# MbrdA_rev2_180.net
KiCad netlist of a schematic drawn in EAGLE
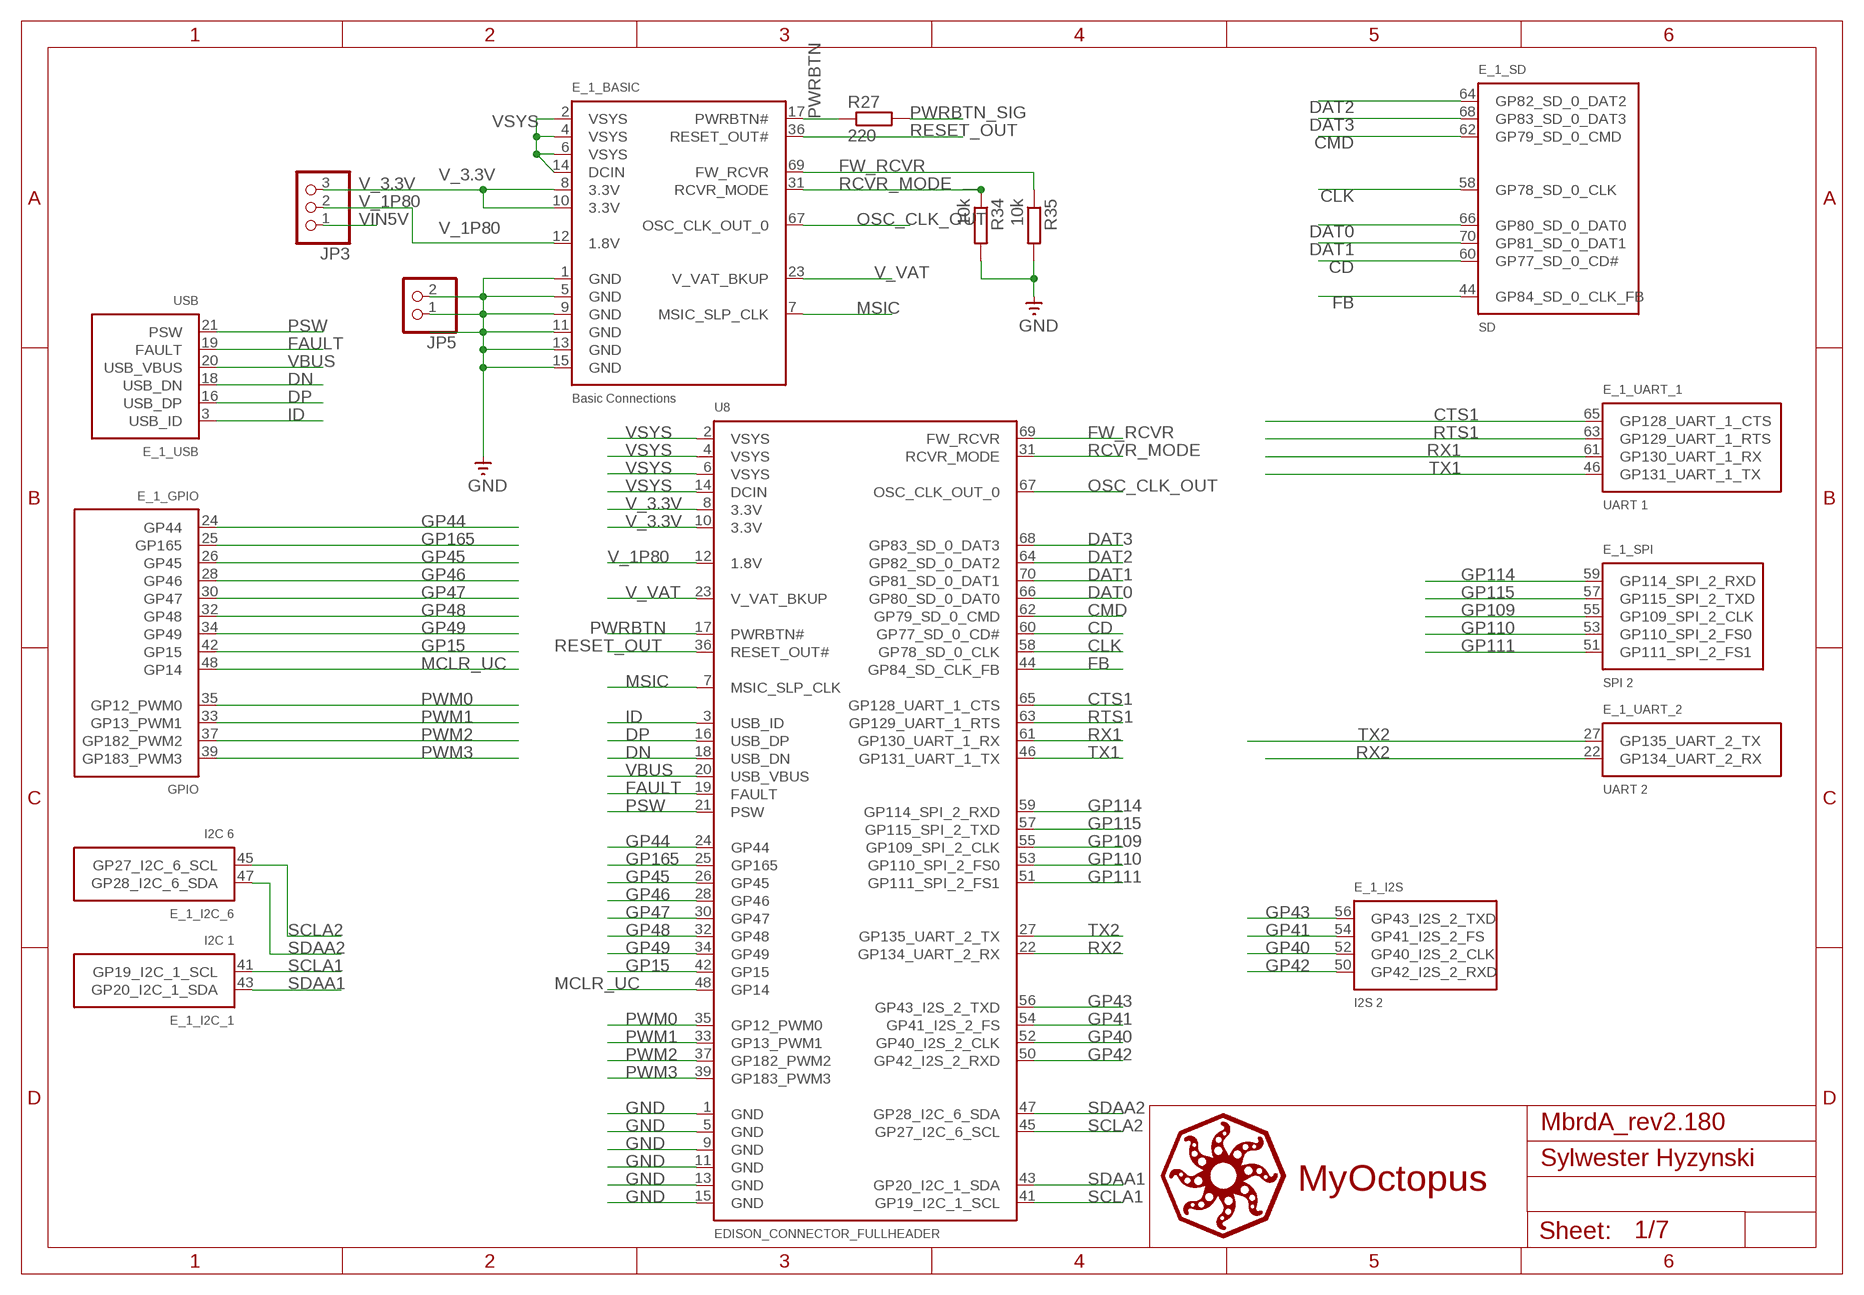
[diagram p0: schematic, sheet 1]
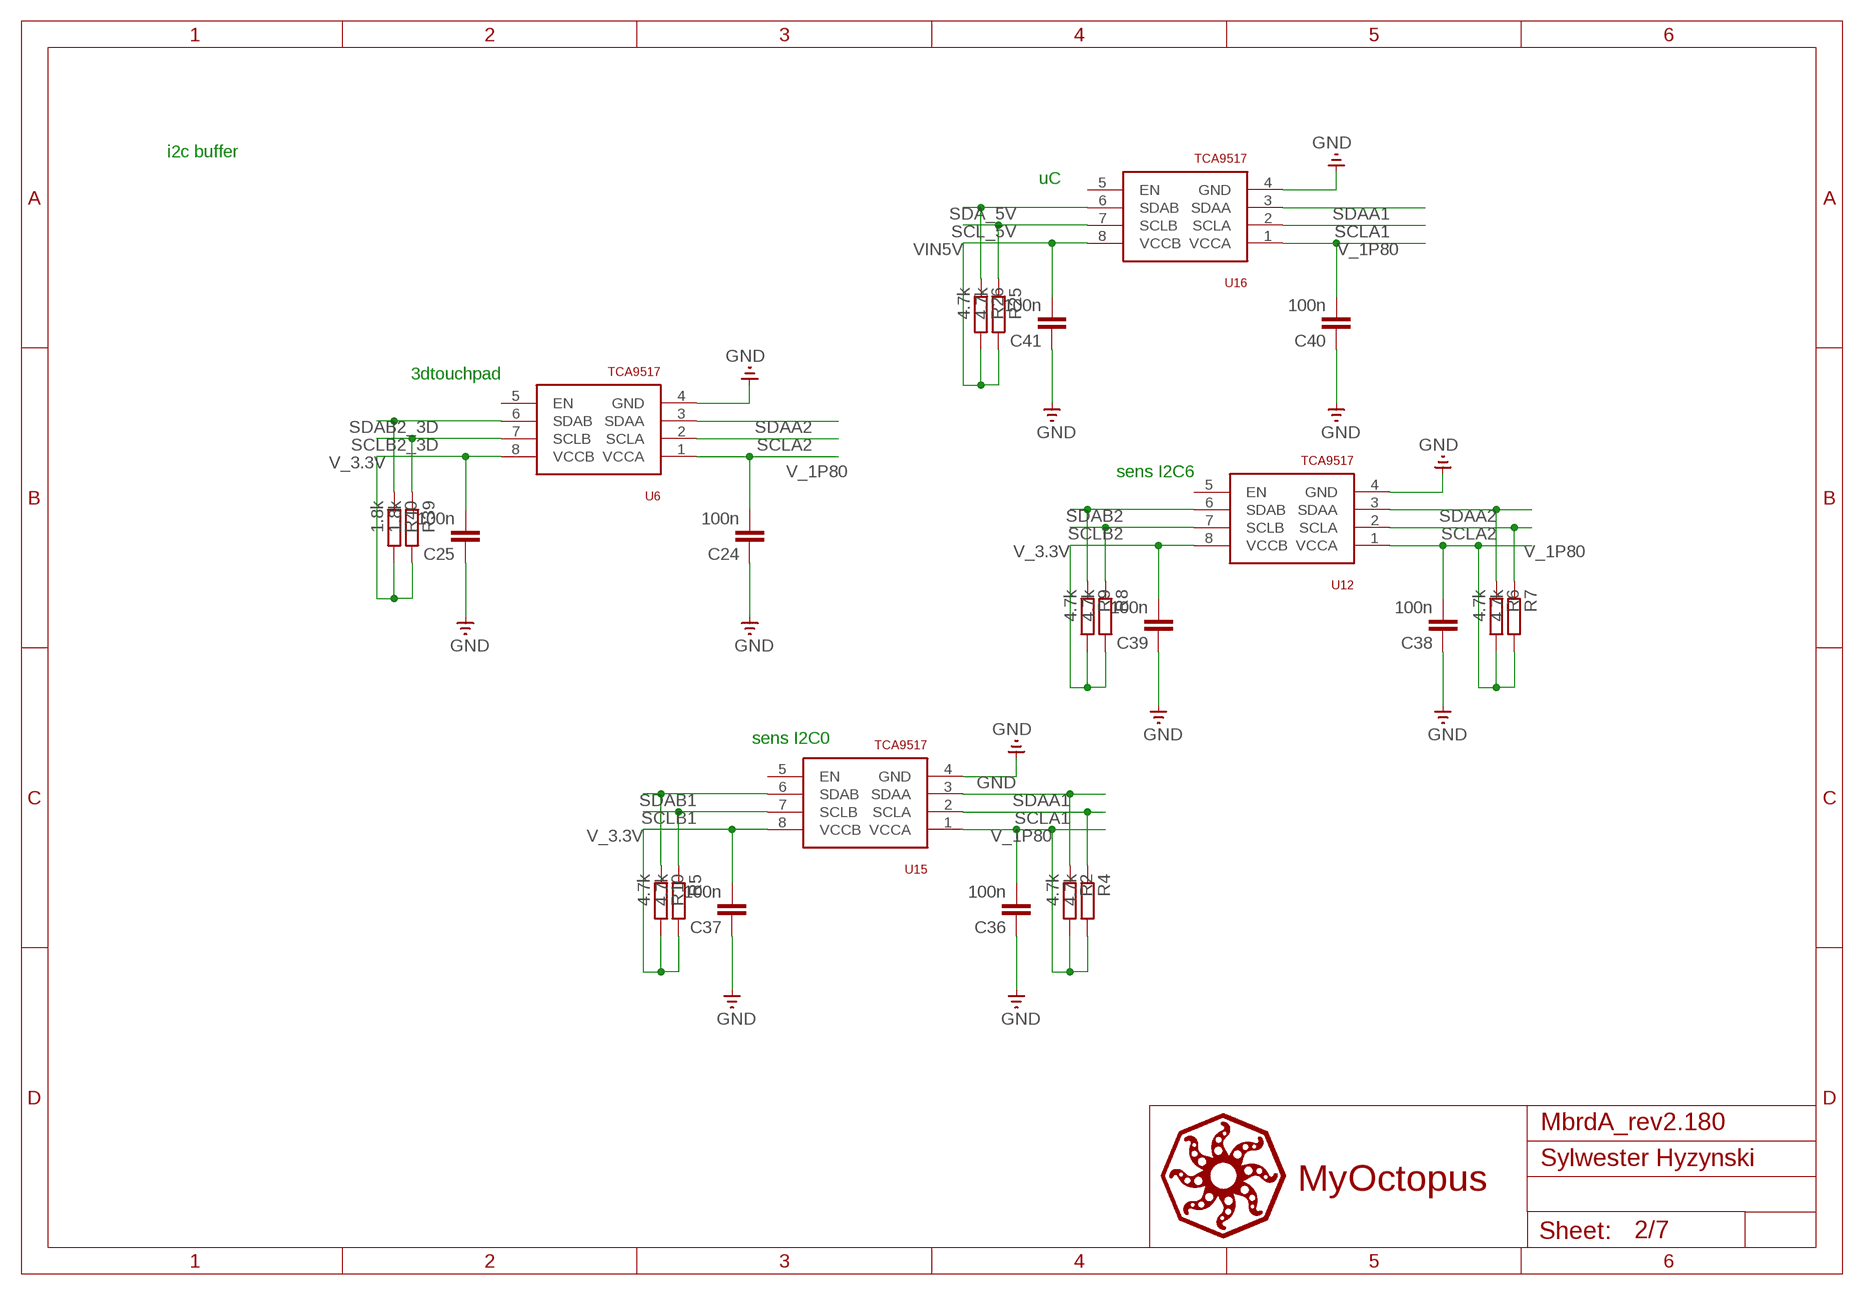
[diagram p1: schematic, sheet 2]
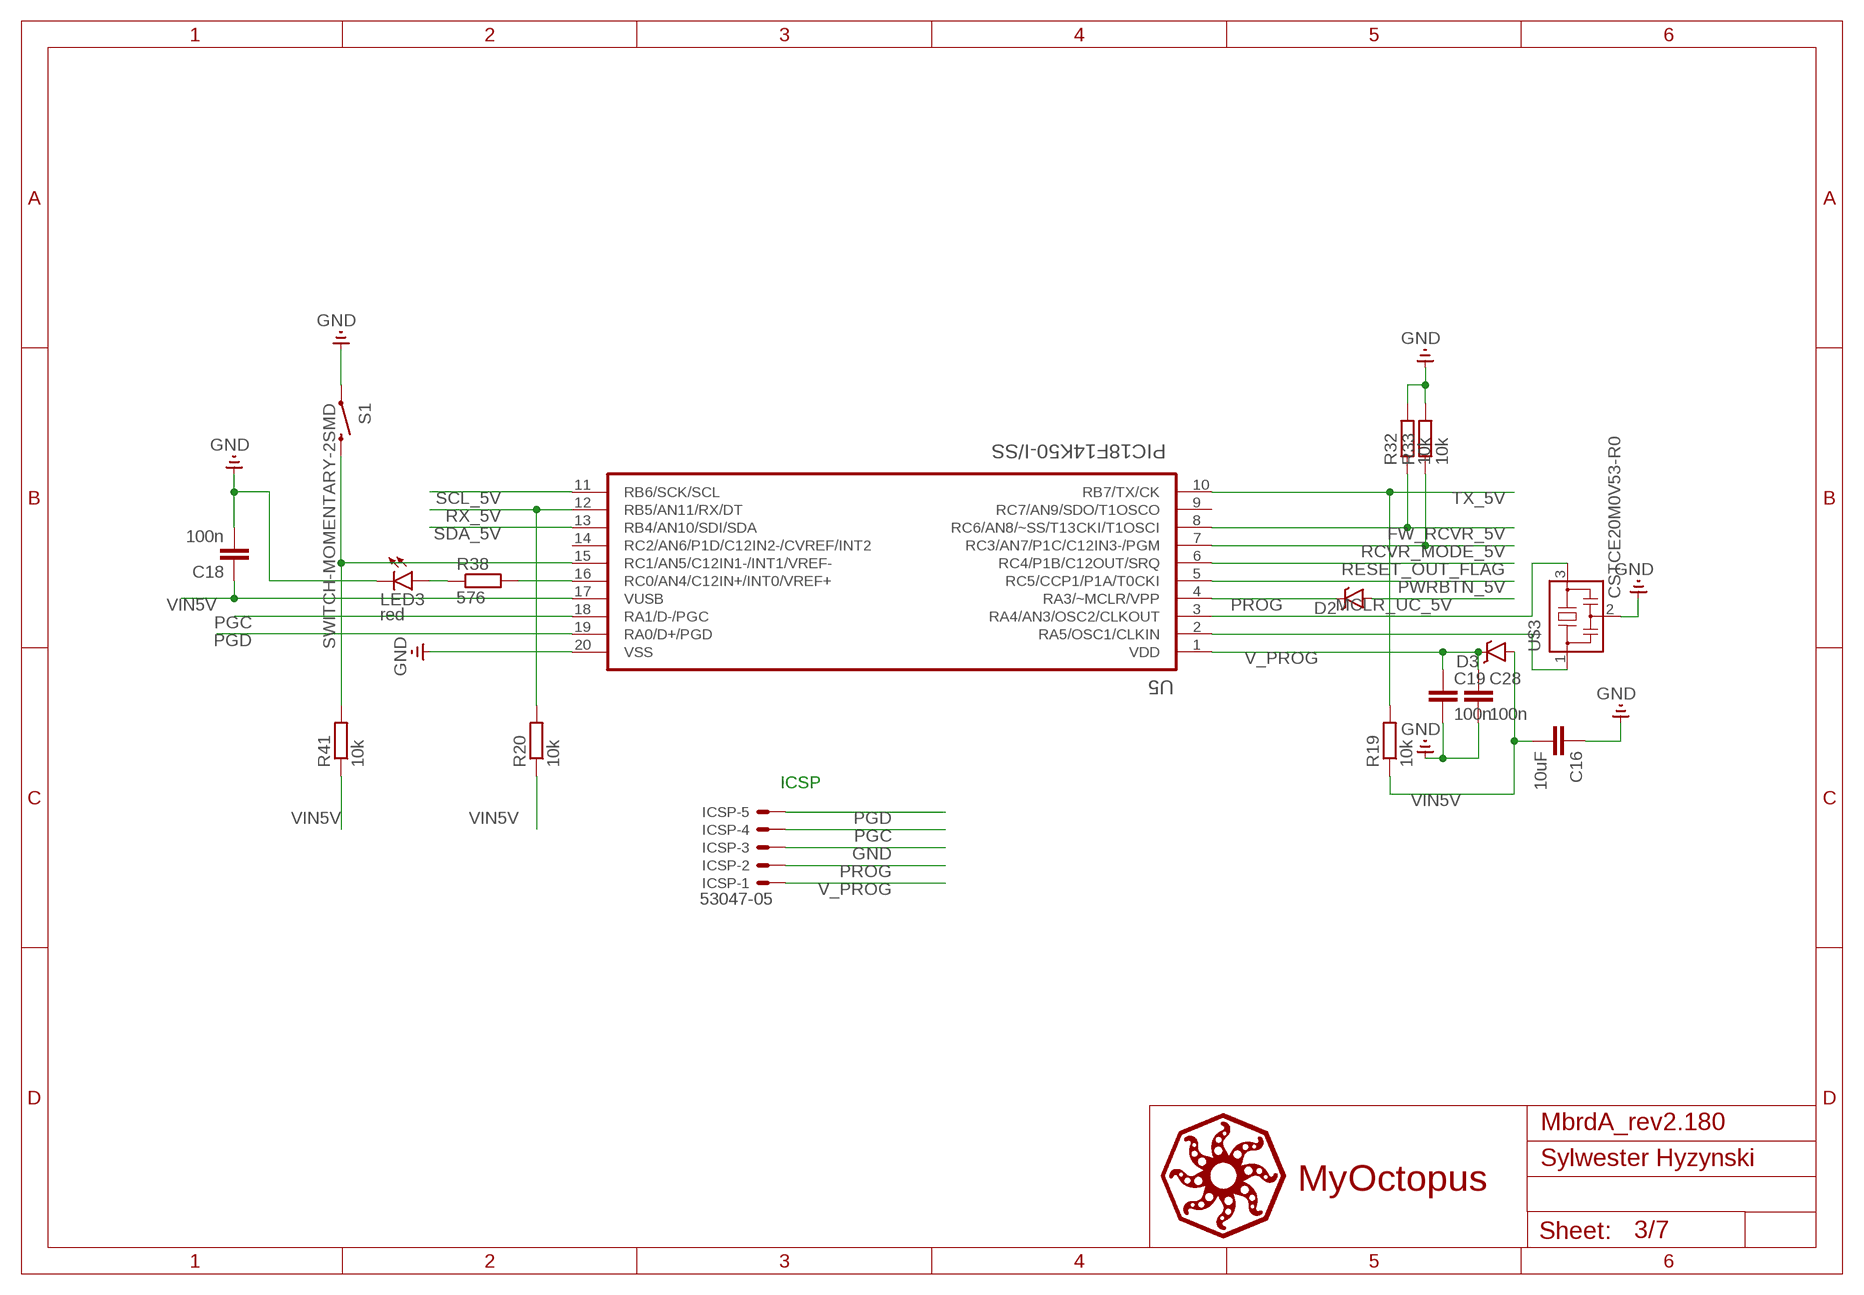
[diagram p2: schematic, sheet 3]
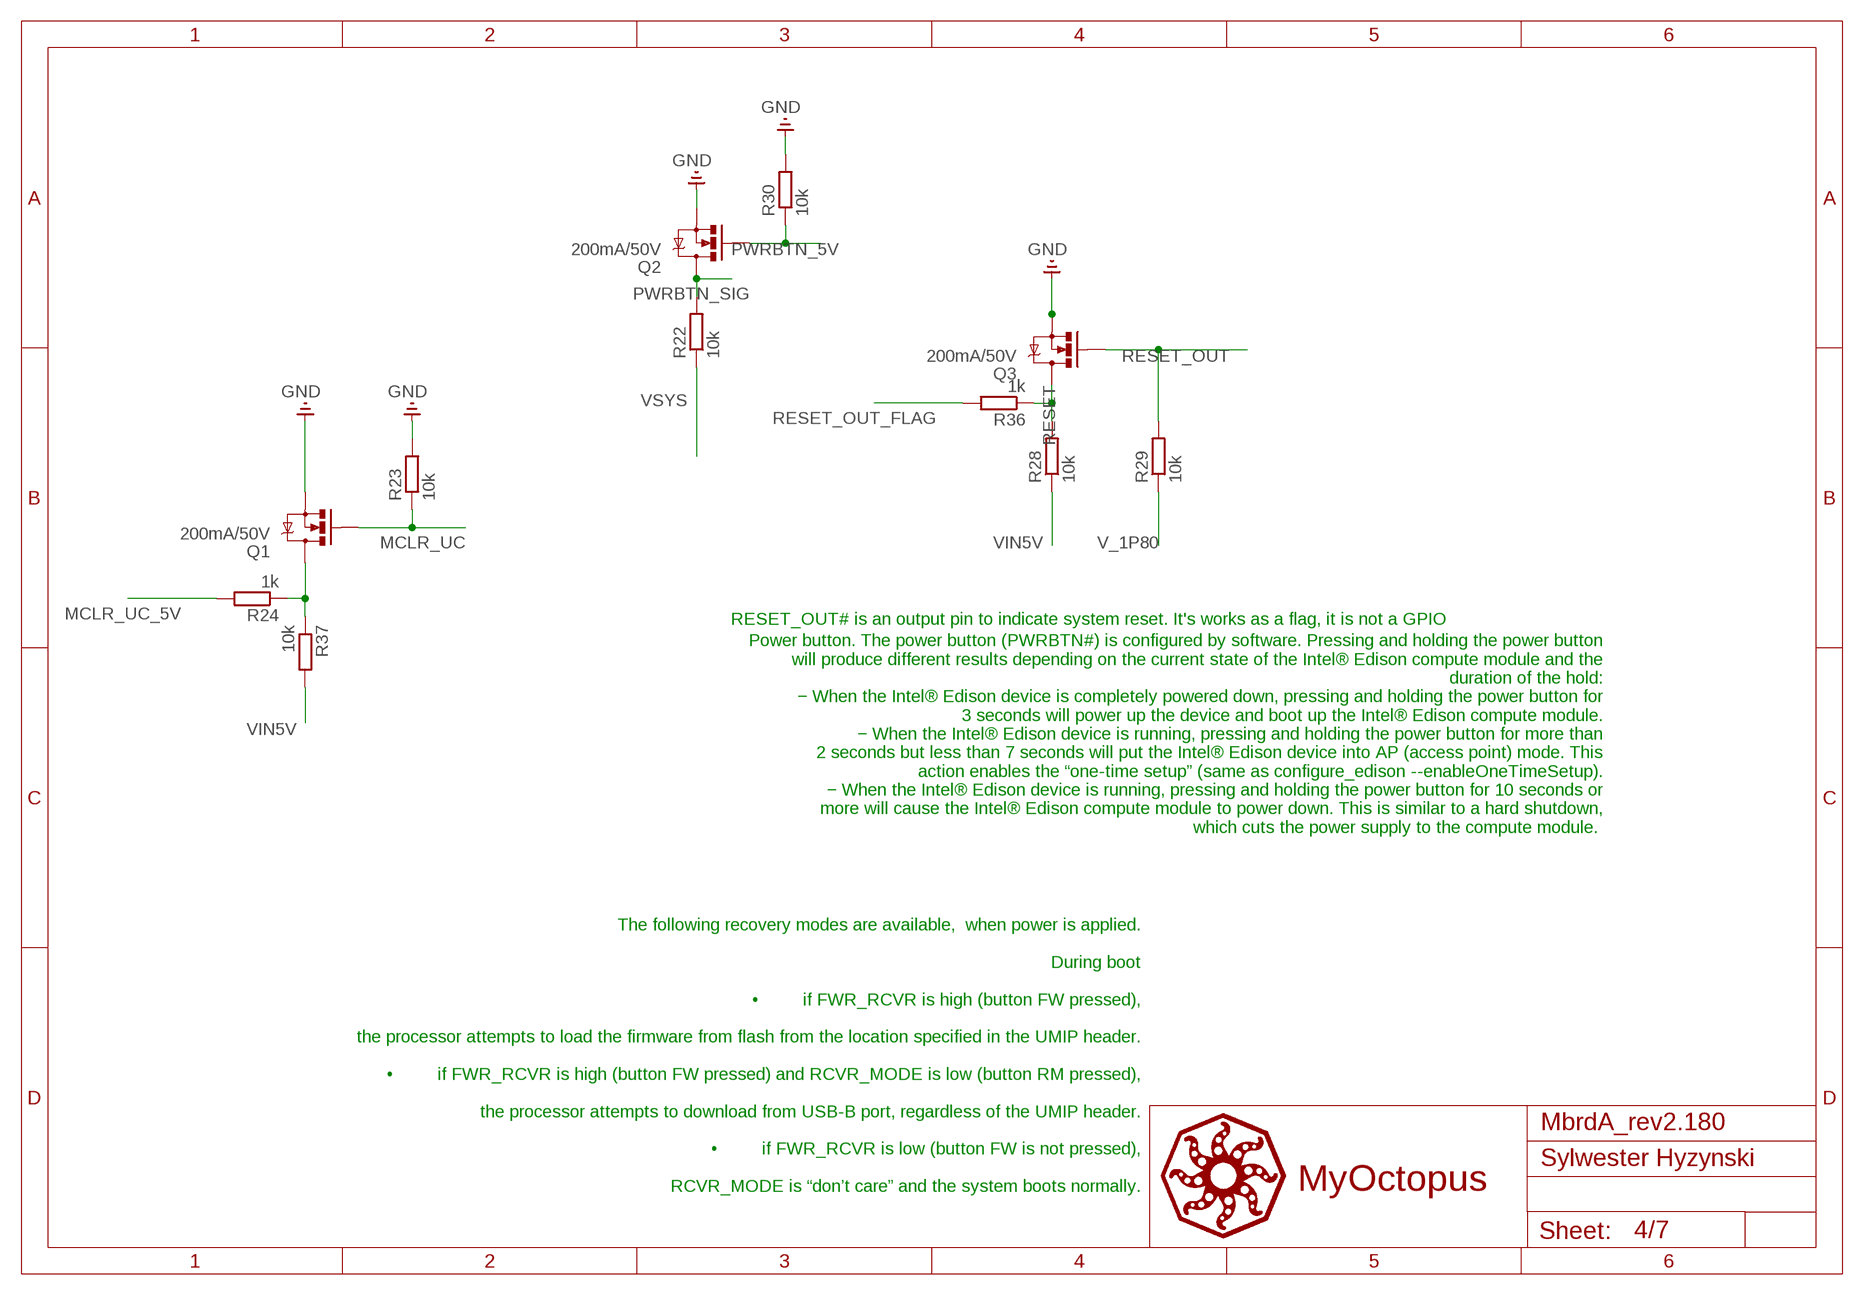
[diagram p3: schematic, sheet 4]
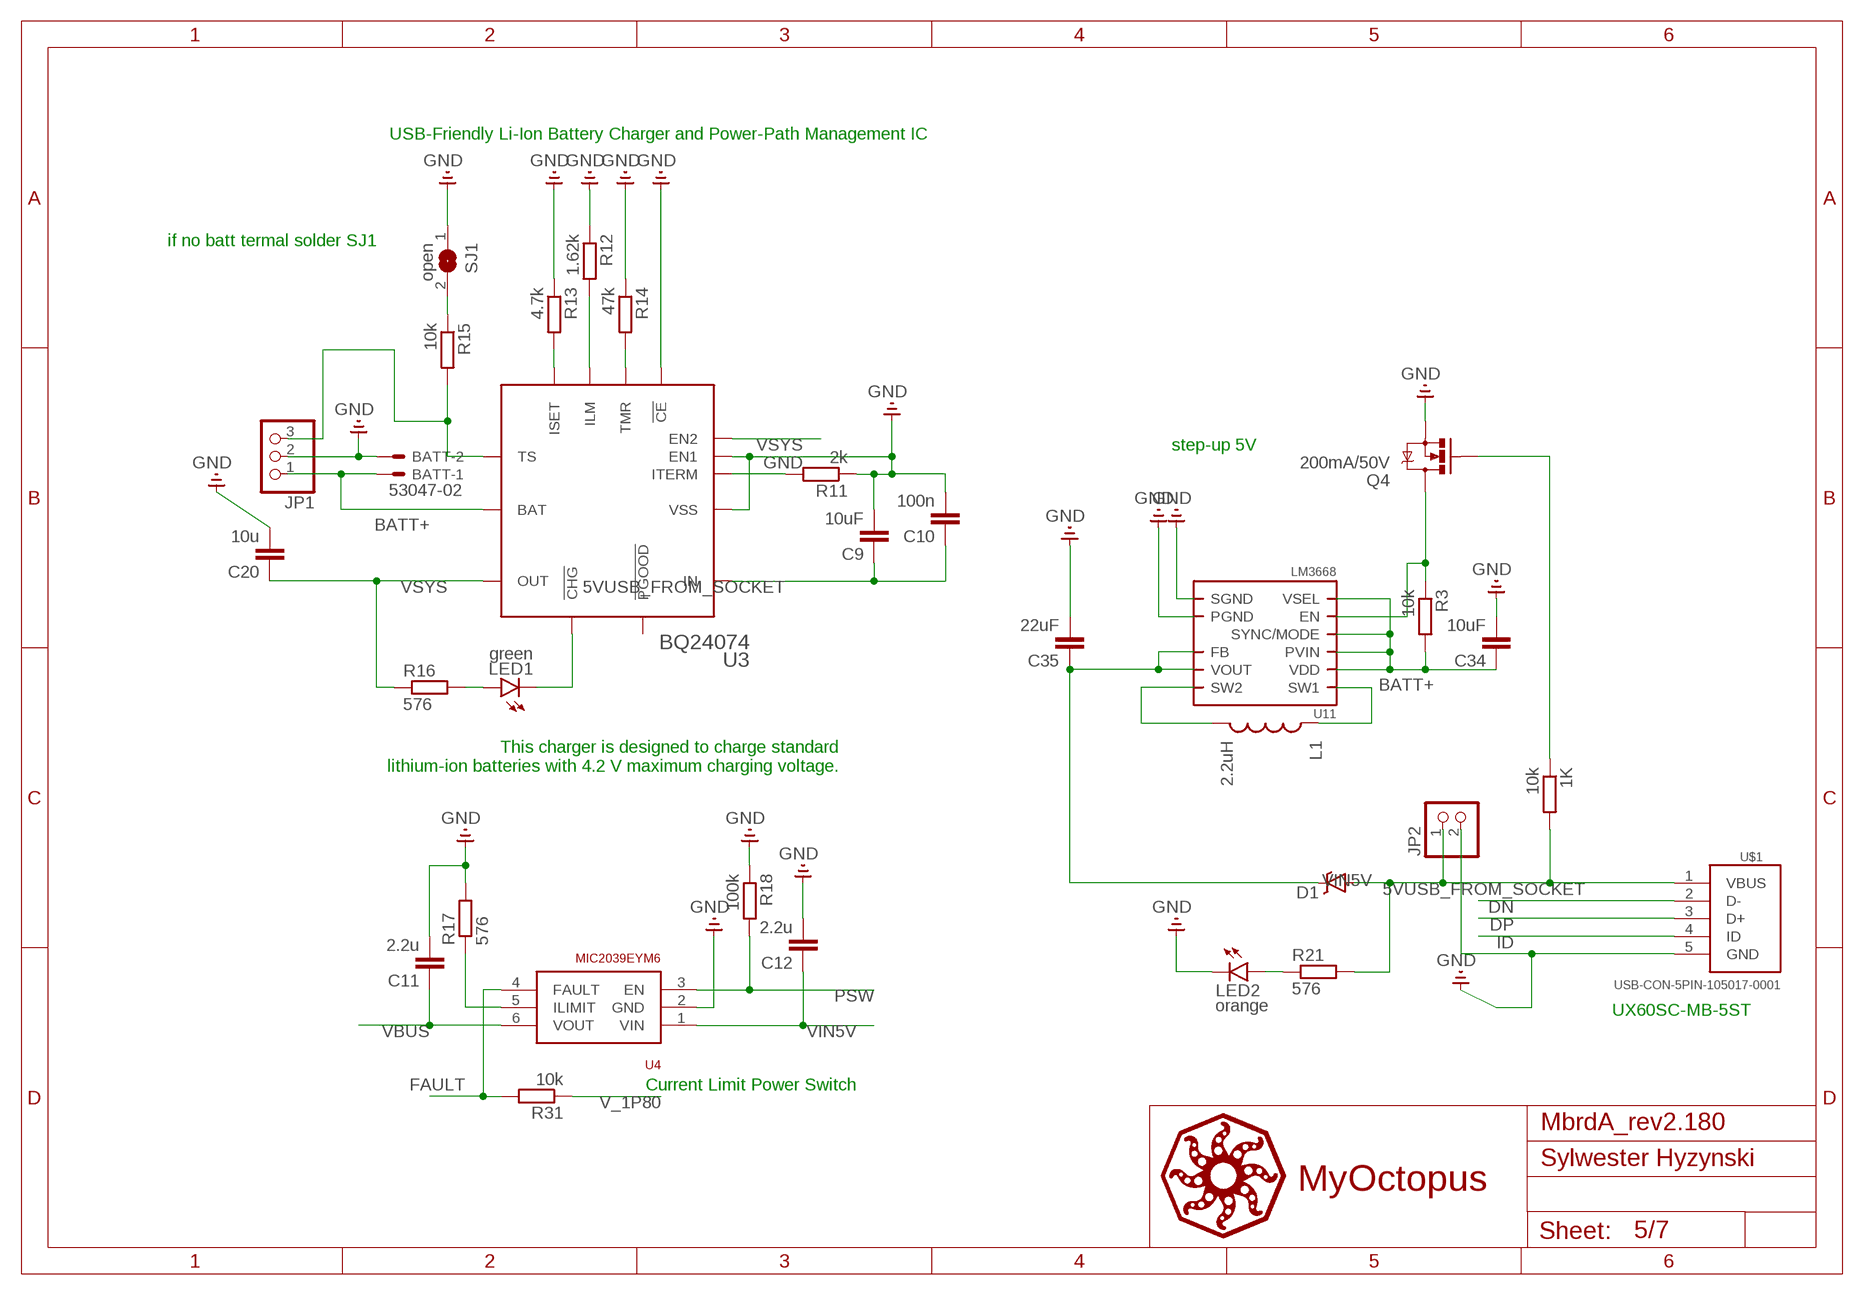
[diagram p4: schematic, sheet 5]
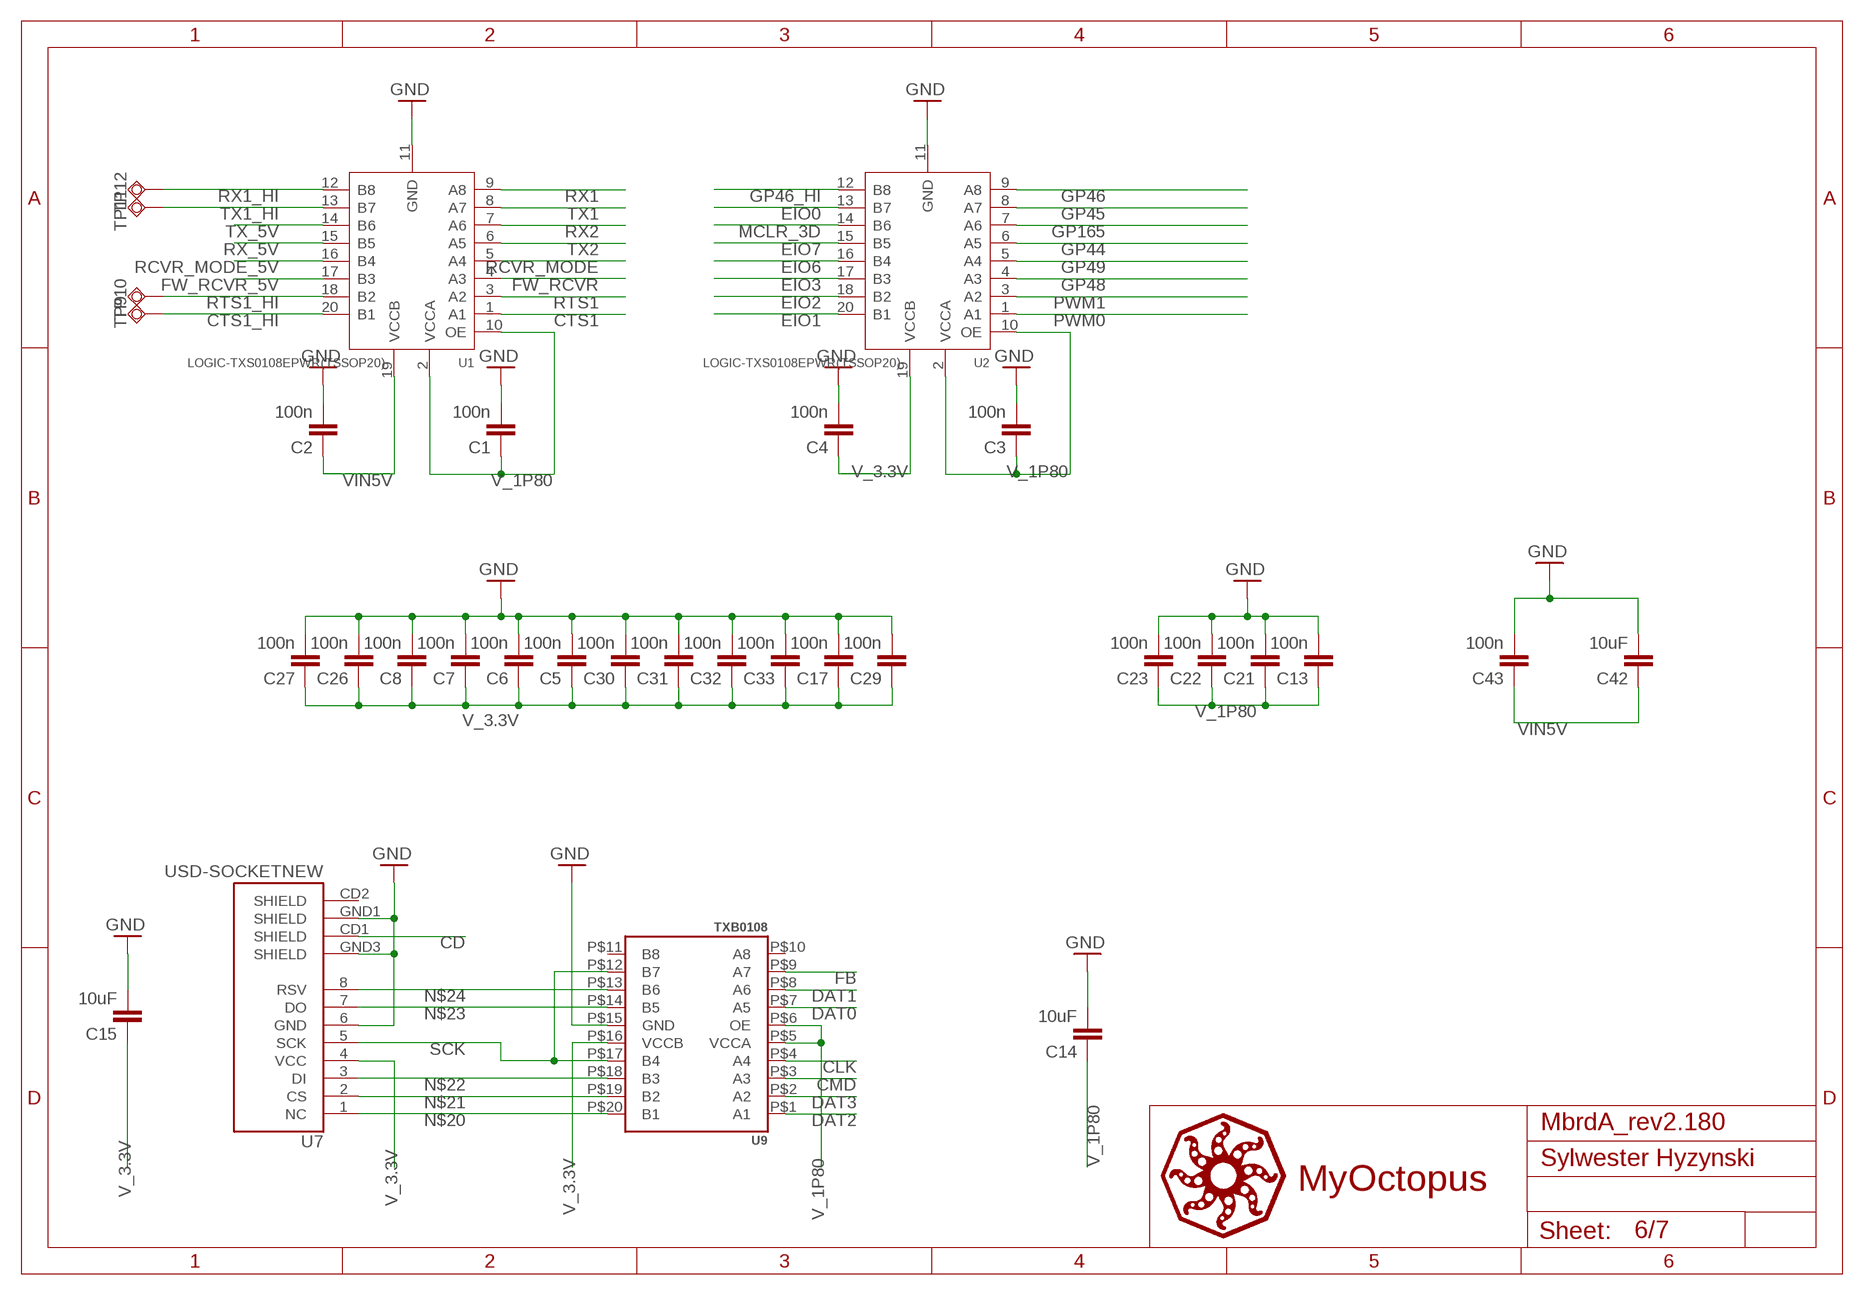
[diagram p5: schematic, sheet 6]
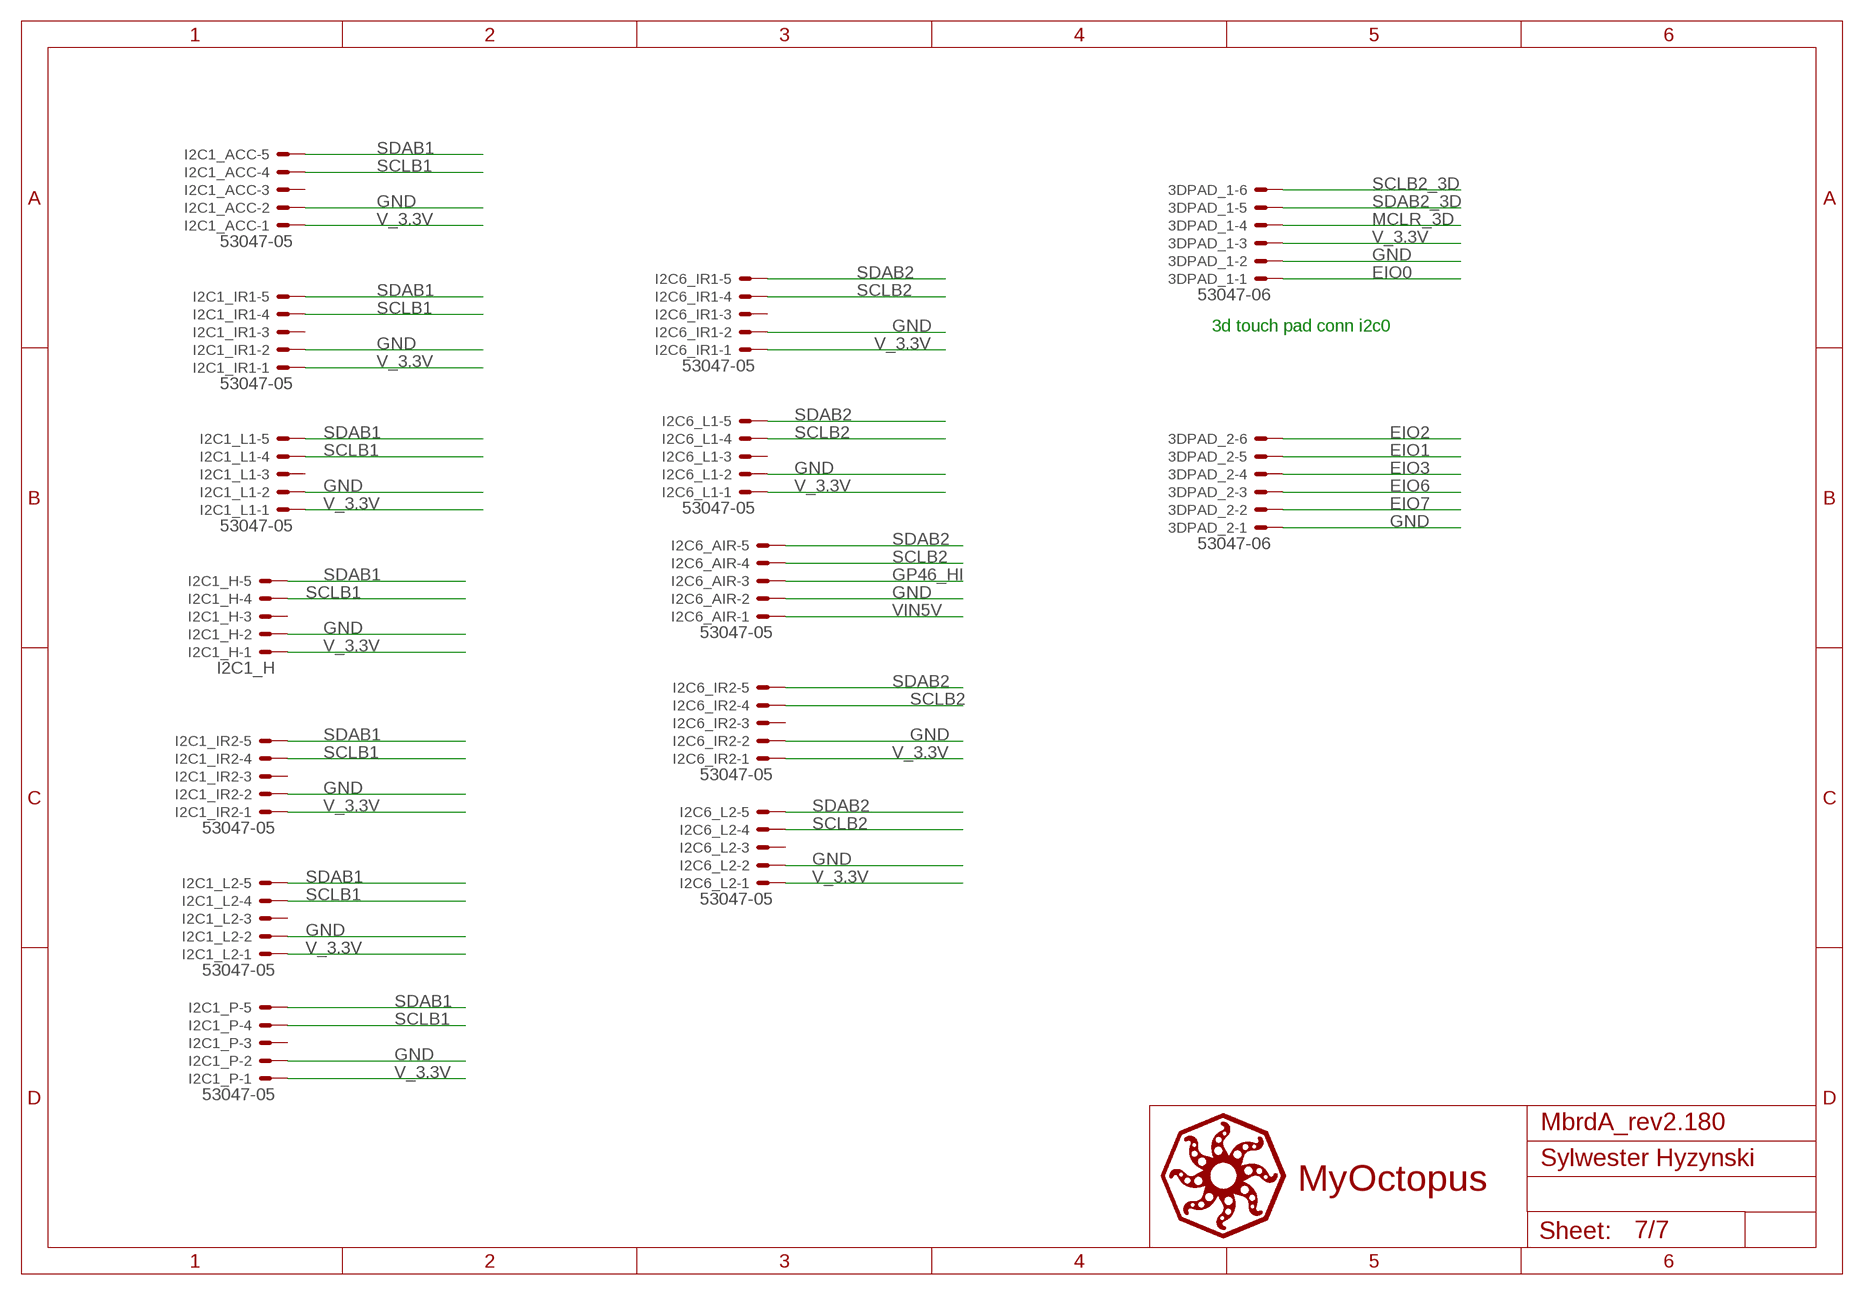
[diagram p6: schematic, sheet 7]

(export (version "E")
  (design (tool "Eeschema 10.0.6"))
  (components
    (comp (ref "1K")
      (value "10k")
      (footprint "eagle-import:R0201")
      (libsource (lib "eagle-import") (part "R-EU_R0201"))
    )
    (comp (ref "BATT")
      (value "53047-02")
      (footprint "eagle-import:53047-02")
      (fields (field (name "MF") "MOLEX") (field (name "MPN") "53047-0210"))
      (libsource (lib "eagle-import") (part "53?-02047"))
    )
    (comp (ref "C9")
      (value "10uF")
      (footprint "eagle-import:C0402")
      (libsource (lib "eagle-import") (part "rcl-2_C-EUC0402"))
    )
    (comp (ref "C10")
      (value "100n")
      (footprint "eagle-import:C0201")
      (libsource (lib "eagle-import") (part "C-EUC0201"))
    )
    (comp (ref "C11")
      (value "2.2u")
      (footprint "eagle-import:C0603")
      (libsource (lib "eagle-import") (part "C-EUC0603"))
    )
    (comp (ref "C12")
      (value "2.2u")
      (footprint "eagle-import:C0603")
      (libsource (lib "eagle-import") (part "C-EUC0603"))
    )
    (comp (ref "C20")
      (value "10u")
      (footprint "eagle-import:C0402")
      (libsource (lib "eagle-import") (part "rcl-2_C-EUC0402"))
    )
    (comp (ref "C34")
      (value "10uF")
      (footprint "eagle-import:C0805")
      (libsource (lib "eagle-import") (part "C-EUC0805"))
    )
    (comp (ref "C35")
      (value "22uF")
      (footprint "eagle-import:C0805")
      (libsource (lib "eagle-import") (part "C-EUC0805"))
    )
    (comp (ref "D1")
      (value "DB2W31900L")
      (footprint "eagle-import:MINI-F3-B")
      (libsource (lib "eagle-import") (part "DB2W31900L"))
    )
    (comp (ref "JP1")
      (value "PINHD-1X3")
      (footprint "eagle-import:1X03")
      (libsource (lib "eagle-import") (part "PINHD-1X3"))
    )
    (comp (ref "JP2")
      (value "PINHD-1X2")
      (footprint "eagle-import:1X02")
      (libsource (lib "eagle-import") (part "PINHD-1X2"))
    )
    (comp (ref "L1")
      (value "2.2uH")
      (footprint "eagle-import:LPS4018")
      (libsource (lib "eagle-import") (part "LPS4018"))
    )
    (comp (ref "LED1")
      (value "green")
      (footprint "eagle-import:LED0402")
      (libsource (lib "eagle-import") (part "LED0402"))
    )
    (comp (ref "LED2")
      (value "orange")
      (footprint "eagle-import:LED0402")
      (libsource (lib "eagle-import") (part "LED0402"))
    )
    (comp (ref "Q4")
      (value "200mA/50V")
      (footprint "eagle-import:SOT23-3")
      (libsource (lib "eagle-import") (part "MOSFET-NCHANNELBSS138"))
    )
    (comp (ref "R3")
      (value "10k")
      (footprint "eagle-import:R0201")
      (libsource (lib "eagle-import") (part "R-EU_R0201"))
    )
    (comp (ref "R11")
      (value "2k")
      (footprint "eagle-import:R0201")
      (libsource (lib "eagle-import") (part "R-EU_R0201"))
    )
    (comp (ref "R12")
      (value "1.62k")
      (footprint "eagle-import:R0201")
      (libsource (lib "eagle-import") (part "R-EU_R0201"))
    )
    (comp (ref "R13")
      (value "4.7k")
      (footprint "eagle-import:R0201")
      (libsource (lib "eagle-import") (part "R-EU_R0201"))
    )
    (comp (ref "R14")
      (value "47k")
      (footprint "eagle-import:R0201")
      (libsource (lib "eagle-import") (part "R-EU_R0201"))
    )
    (comp (ref "R15")
      (value "10k")
      (footprint "eagle-import:R0201")
      (libsource (lib "eagle-import") (part "R-EU_R0201"))
    )
    (comp (ref "R16")
      (value "576")
      (footprint "eagle-import:R0201")
      (libsource (lib "eagle-import") (part "R-EU_R0201"))
    )
    (comp (ref "R17")
      (value "576")
      (footprint "eagle-import:R0201")
      (libsource (lib "eagle-import") (part "R-EU_R0201"))
    )
    (comp (ref "R18")
      (value "100k")
      (footprint "eagle-import:R0201")
      (libsource (lib "eagle-import") (part "R-EU_R0201"))
    )
    (comp (ref "R21")
      (value "576")
      (footprint "eagle-import:R0201")
      (libsource (lib "eagle-import") (part "R-EU_R0201"))
    )
    (comp (ref "R31")
      (value "10k")
      (footprint "eagle-import:R0201")
      (libsource (lib "eagle-import") (part "R-EU_R0201"))
    )
    (comp (ref "SJ1")
      (value "open")
      (footprint "eagle-import:SJ")
      (libsource (lib "eagle-import") (part "SJ"))
    )
    (comp (ref "U$1")
      (value "USB-CON-5PIN-105017-0001")
      (footprint "eagle-import:USB-MICRO-MOLEX-105017-0001")
      (libsource (lib "eagle-import") (part "USB-CON-5PIN-105017-0001"))
    )
    (comp (ref "U3")
      (value "BQ24074")
      (footprint "eagle-import:QFN-16_BOT_PAD")
      (libsource (lib "eagle-import") (part "BQ2407XQFN-16"))
    )
    (comp (ref "U4")
      (value "MIC2039EYM6")
      (footprint "eagle-import:SOT23-6L")
      (libsource (lib "eagle-import") (part "MIC2039EYM6"))
    )
    (comp (ref "U11")
      (value "LM3668")
      (footprint "eagle-import:LLP.12.3X3MM")
      (libsource (lib "eagle-import") (part "LM3668"))
    )
    (comp (ref "C24")
      (value "100n")
      (footprint "eagle-import:C0201")
      (libsource (lib "eagle-import") (part "C-EUC0201"))
    )
    (comp (ref "C25")
      (value "100n")
      (footprint "eagle-import:C0201")
      (libsource (lib "eagle-import") (part "C-EUC0201"))
    )
    (comp (ref "C36")
      (value "100n")
      (footprint "eagle-import:C0201")
      (libsource (lib "eagle-import") (part "C-EUC0201"))
    )
    (comp (ref "C37")
      (value "100n")
      (footprint "eagle-import:C0201")
      (libsource (lib "eagle-import") (part "C-EUC0201"))
    )
    (comp (ref "C38")
      (value "100n")
      (footprint "eagle-import:C0201")
      (libsource (lib "eagle-import") (part "C-EUC0201"))
    )
    (comp (ref "C39")
      (value "100n")
      (footprint "eagle-import:C0201")
      (libsource (lib "eagle-import") (part "C-EUC0201"))
    )
    (comp (ref "C40")
      (value "100n")
      (footprint "eagle-import:C0201")
      (libsource (lib "eagle-import") (part "C-EUC0201"))
    )
    (comp (ref "C41")
      (value "100n")
      (footprint "eagle-import:C0201")
      (libsource (lib "eagle-import") (part "C-EUC0201"))
    )
    (comp (ref "R2")
      (value "4.7k")
      (footprint "eagle-import:R0201")
      (libsource (lib "eagle-import") (part "R-EU_R0201"))
    )
    (comp (ref "R4")
      (value "4.7k")
      (footprint "eagle-import:R0201")
      (libsource (lib "eagle-import") (part "R-EU_R0201"))
    )
    (comp (ref "R5")
      (value "4.7k")
      (footprint "eagle-import:R0201")
      (libsource (lib "eagle-import") (part "R-EU_R0201"))
    )
    (comp (ref "R6")
      (value "4.7k")
      (footprint "eagle-import:R0201")
      (libsource (lib "eagle-import") (part "R-EU_R0201"))
    )
    (comp (ref "R7")
      (value "4.7k")
      (footprint "eagle-import:R0201")
      (libsource (lib "eagle-import") (part "R-EU_R0201"))
    )
    (comp (ref "R8")
      (value "4.7k")
      (footprint "eagle-import:R0201")
      (libsource (lib "eagle-import") (part "R-EU_R0201"))
    )
    (comp (ref "R9")
      (value "4.7k")
      (footprint "eagle-import:R0201")
      (libsource (lib "eagle-import") (part "R-EU_R0201"))
    )
    (comp (ref "R10")
      (value "4.7k")
      (footprint "eagle-import:R0201")
      (libsource (lib "eagle-import") (part "R-EU_R0201"))
    )
    (comp (ref "R25")
      (value "4.7k")
      (footprint "eagle-import:R0201")
      (libsource (lib "eagle-import") (part "R-EU_R0201"))
    )
    (comp (ref "R26")
      (value "4.7k")
      (footprint "eagle-import:R0201")
      (libsource (lib "eagle-import") (part "R-EU_R0201"))
    )
    (comp (ref "R39")
      (value "1.8k")
      (footprint "eagle-import:R0201")
      (libsource (lib "eagle-import") (part "R-EU_R0201"))
    )
    (comp (ref "R40")
      (value "1.8k")
      (footprint "eagle-import:R0201")
      (libsource (lib "eagle-import") (part "R-EU_R0201"))
    )
    (comp (ref "U6")
      (value "TCA9517")
      (footprint "eagle-import:SO-08")
      (libsource (lib "eagle-import") (part "TCA9517"))
    )
    (comp (ref "U12")
      (value "TCA9517")
      (footprint "eagle-import:SO-08")
      (libsource (lib "eagle-import") (part "TCA9517"))
    )
    (comp (ref "U15")
      (value "TCA9517")
      (footprint "eagle-import:SO-08")
      (libsource (lib "eagle-import") (part "TCA9517"))
    )
    (comp (ref "U16")
      (value "TCA9517")
      (footprint "eagle-import:SO-08")
      (libsource (lib "eagle-import") (part "TCA9517"))
    )
    (comp (ref "C16")
      (value "10uF")
      (footprint "eagle-import:C0402")
      (libsource (lib "eagle-import") (part "rcl-2_C-EUC0402"))
    )
    (comp (ref "C18")
      (value "100n")
      (footprint "eagle-import:C0201")
      (libsource (lib "eagle-import") (part "C-EUC0201"))
    )
    (comp (ref "C19")
      (value "100n")
      (footprint "eagle-import:C0201")
      (libsource (lib "eagle-import") (part "C-EUC0201"))
    )
    (comp (ref "C28")
      (value "100n")
      (footprint "eagle-import:C0201")
      (libsource (lib "eagle-import") (part "C-EUC0201"))
    )
    (comp (ref "D2")
      (value "DB2W31900L")
      (footprint "eagle-import:MINI-F3-B")
      (libsource (lib "eagle-import") (part "DB2W31900L"))
    )
    (comp (ref "D3")
      (value "DB2W31900L")
      (footprint "eagle-import:MINI-F3-B")
      (libsource (lib "eagle-import") (part "DB2W31900L"))
    )
    (comp (ref "ICSP")
      (value "53047-05")
      (footprint "eagle-import:53047-05")
      (fields (field (name "MF") "MOLEX") (field (name "MPN") "53047-0510"))
      (libsource (lib "eagle-import") (part "53?-05047"))
    )
    (comp (ref "LED3")
      (value "red")
      (footprint "eagle-import:LED0402")
      (libsource (lib "eagle-import") (part "LED0402"))
    )
    (comp (ref "R19")
      (value "10k")
      (footprint "eagle-import:R0201")
      (libsource (lib "eagle-import") (part "R-EU_R0201"))
    )
    (comp (ref "R20")
      (value "10k")
      (footprint "eagle-import:R0201")
      (libsource (lib "eagle-import") (part "R-EU_R0201"))
    )
    (comp (ref "R32")
      (value "10k")
      (footprint "eagle-import:R0201")
      (libsource (lib "eagle-import") (part "R-EU_R0201"))
    )
    (comp (ref "R33")
      (value "10k")
      (footprint "eagle-import:R0201")
      (libsource (lib "eagle-import") (part "R-EU_R0201"))
    )
    (comp (ref "R38")
      (value "576")
      (footprint "eagle-import:R0201")
      (libsource (lib "eagle-import") (part "R-EU_R0201"))
    )
    (comp (ref "R41")
      (value "10k")
      (footprint "eagle-import:R0201")
      (libsource (lib "eagle-import") (part "R-EU_R0201"))
    )
    (comp (ref "S1")
      (value "SWITCH-MOMENTARY-2SMD")
      (footprint "eagle-import:TACTILE_SWITCH_SMD")
      (libsource (lib "eagle-import") (part "SWITCH-MOMENTARY-2SMD"))
    )
    (comp (ref "U$3")
      (value "CSTCE20M0V53-R0")
      (footprint "eagle-import:CSTER12M")
      (libsource (lib "eagle-import") (part "CSTCE20M0V53-R0"))
    )
    (comp (ref "U5")
      (value "PIC18F14K50-I/SS")
      (footprint "eagle-import:SOP65P780X200-20N")
      (libsource (lib "eagle-import") (part "PIC18F14K50-I/SS"))
    )
    (comp (ref "C1")
      (value "100n")
      (footprint "eagle-import:C0201")
      (libsource (lib "eagle-import") (part "C-EUC0201"))
    )
    (comp (ref "C2")
      (value "100n")
      (footprint "eagle-import:C0201")
      (libsource (lib "eagle-import") (part "C-EUC0201"))
    )
    (comp (ref "C3")
      (value "100n")
      (footprint "eagle-import:C0201")
      (libsource (lib "eagle-import") (part "C-EUC0201"))
    )
    (comp (ref "C4")
      (value "100n")
      (footprint "eagle-import:C0201")
      (libsource (lib "eagle-import") (part "C-EUC0201"))
    )
    (comp (ref "C5")
      (value "100n")
      (footprint "eagle-import:C0201")
      (libsource (lib "eagle-import") (part "C-EUC0201"))
    )
    (comp (ref "C6")
      (value "100n")
      (footprint "eagle-import:C0201")
      (libsource (lib "eagle-import") (part "C-EUC0201"))
    )
    (comp (ref "C7")
      (value "100n")
      (footprint "eagle-import:C0201")
      (libsource (lib "eagle-import") (part "C-EUC0201"))
    )
    (comp (ref "C8")
      (value "100n")
      (footprint "eagle-import:C0201")
      (libsource (lib "eagle-import") (part "C-EUC0201"))
    )
    (comp (ref "C13")
      (value "100n")
      (footprint "eagle-import:C0201")
      (libsource (lib "eagle-import") (part "C-EUC0201"))
    )
    (comp (ref "C14")
      (value "10uF")
      (footprint "eagle-import:C0402")
      (libsource (lib "eagle-import") (part "rcl-2_C-EUC0402"))
    )
    (comp (ref "C15")
      (value "10uF")
      (footprint "eagle-import:C0402")
      (libsource (lib "eagle-import") (part "rcl-2_C-EUC0402"))
    )
    (comp (ref "C17")
      (value "100n")
      (footprint "eagle-import:C0201")
      (libsource (lib "eagle-import") (part "C-EUC0201"))
    )
    (comp (ref "C21")
      (value "100n")
      (footprint "eagle-import:C0201")
      (libsource (lib "eagle-import") (part "C-EUC0201"))
    )
    (comp (ref "C22")
      (value "100n")
      (footprint "eagle-import:C0201")
      (libsource (lib "eagle-import") (part "C-EUC0201"))
    )
    (comp (ref "C23")
      (value "100n")
      (footprint "eagle-import:C0201")
      (libsource (lib "eagle-import") (part "C-EUC0201"))
    )
    (comp (ref "C26")
      (value "100n")
      (footprint "eagle-import:C0201")
      (libsource (lib "eagle-import") (part "C-EUC0201"))
    )
    (comp (ref "C27")
      (value "100n")
      (footprint "eagle-import:C0201")
      (libsource (lib "eagle-import") (part "C-EUC0201"))
    )
    (comp (ref "C29")
      (value "100n")
      (footprint "eagle-import:C0201")
      (libsource (lib "eagle-import") (part "C-EUC0201"))
    )
    (comp (ref "C30")
      (value "100n")
      (footprint "eagle-import:C0201")
      (libsource (lib "eagle-import") (part "C-EUC0201"))
    )
    (comp (ref "C31")
      (value "100n")
      (footprint "eagle-import:C0201")
      (libsource (lib "eagle-import") (part "C-EUC0201"))
    )
    (comp (ref "C32")
      (value "100n")
      (footprint "eagle-import:C0201")
      (libsource (lib "eagle-import") (part "C-EUC0201"))
    )
    (comp (ref "C33")
      (value "100n")
      (footprint "eagle-import:C0201")
      (libsource (lib "eagle-import") (part "C-EUC0201"))
    )
    (comp (ref "C42")
      (value "10uF")
      (footprint "eagle-import:C0805")
      (libsource (lib "eagle-import") (part "C-EUC0805"))
    )
    (comp (ref "C43")
      (value "100n")
      (footprint "eagle-import:C0201")
      (libsource (lib "eagle-import") (part "C-EUC0201"))
    )
    (comp (ref "TP9")
      (value "TPSQPAD1-13")
      (footprint "eagle-import:P1-13")
      (libsource (lib "eagle-import") (part "TPSQPAD1-13"))
    )
    (comp (ref "TP10")
      (value "TPSQPAD1-13")
      (footprint "eagle-import:P1-13")
      (libsource (lib "eagle-import") (part "TPSQPAD1-13"))
    )
    (comp (ref "TP11")
      (value "TPSQPAD1-13")
      (footprint "eagle-import:P1-13")
      (libsource (lib "eagle-import") (part "TPSQPAD1-13"))
    )
    (comp (ref "TP12")
      (value "TPSQPAD1-13")
      (footprint "eagle-import:P1-13")
      (libsource (lib "eagle-import") (part "TPSQPAD1-13"))
    )
    (comp (ref "U1")
      (value "LOGIC-TXS0108EPWR(TSSOP20)")
      (footprint "eagle-import:TSSOP20-0.65-6.5X4.4MM")
      (fields (field (name "MPN") "TXS0108EPWR"))
      (libsource (lib "eagle-import") (part "LOGIC-TXS0108EPWR(TSSOP20)"))
    )
    (comp (ref "U2")
      (value "LOGIC-TXS0108EPWR(TSSOP20)")
      (footprint "eagle-import:TSSOP20-0.65-6.5X4.4MM")
      (fields (field (name "MPN") "TXS0108EPWR"))
      (libsource (lib "eagle-import") (part "LOGIC-TXS0108EPWR(TSSOP20)"))
    )
    (comp (ref "U7")
      (value "USD-SOCKETNEW")
      (footprint "eagle-import:MICRO-SD-SOCKET-PP")
      (libsource (lib "eagle-import") (part "USD-SOCKETNEW"))
    )
    (comp (ref "U9")
      (value "TXB0108")
      (footprint "eagle-import:UFDFN-20")
      (libsource (lib "eagle-import") (part "TXB0108"))
    )
    (comp (ref "Q1")
      (value "200mA/50V")
      (footprint "eagle-import:SOT23-3")
      (libsource (lib "eagle-import") (part "MOSFET-NCHANNELBSS138"))
    )
    (comp (ref "Q2")
      (value "200mA/50V")
      (footprint "eagle-import:SOT23-3")
      (libsource (lib "eagle-import") (part "MOSFET-NCHANNELBSS138"))
    )
    (comp (ref "Q3")
      (value "200mA/50V")
      (footprint "eagle-import:SOT23-3")
      (libsource (lib "eagle-import") (part "MOSFET-NCHANNELBSS138"))
    )
    (comp (ref "R22")
      (value "10k")
      (footprint "eagle-import:R0201")
      (libsource (lib "eagle-import") (part "R-EU_R0201"))
    )
    (comp (ref "R23")
      (value "10k")
      (footprint "eagle-import:R0201")
      (libsource (lib "eagle-import") (part "R-EU_R0201"))
    )
    (comp (ref "R24")
      (value "1k")
      (footprint "eagle-import:R0201")
      (libsource (lib "eagle-import") (part "R-EU_R0201"))
    )
    (comp (ref "R28")
      (value "10k")
      (footprint "eagle-import:R0201")
      (libsource (lib "eagle-import") (part "R-EU_R0201"))
    )
    (comp (ref "R29")
      (value "10k")
      (footprint "eagle-import:R0201")
      (libsource (lib "eagle-import") (part "R-EU_R0201"))
    )
    (comp (ref "R30")
      (value "10k")
      (footprint "eagle-import:R0201")
      (libsource (lib "eagle-import") (part "R-EU_R0201"))
    )
    (comp (ref "R36")
      (value "1k")
      (footprint "eagle-import:R0201")
      (libsource (lib "eagle-import") (part "R-EU_R0201"))
    )
    (comp (ref "R37")
      (value "10k")
      (footprint "eagle-import:R0201")
      (libsource (lib "eagle-import") (part "R-EU_R0201"))
    )
    (comp (ref "3DPAD_1")
      (value "53047-06")
      (footprint "eagle-import:53047-06")
      (fields (field (name "MPN") "53047-0610-C"))
      (libsource (lib "eagle-import") (part "53?-06047"))
    )
    (comp (ref "3DPAD_2")
      (value "53047-06")
      (footprint "eagle-import:53047-06")
      (fields (field (name "MPN") "53047-0610-C"))
      (libsource (lib "eagle-import") (part "53?-06047"))
    )
    (comp (ref "I2C1_ACC")
      (value "53047-05")
      (footprint "eagle-import:53047-05")
      (fields (field (name "MF") "MOLEX") (field (name "MPN") "53047-0510"))
      (libsource (lib "eagle-import") (part "53?-05047"))
    )
    (comp (ref "I2C1_H")
      (value "I2C1_H")
      (footprint "eagle-import:53047-05")
      (fields (field (name "MF") "MOLEX") (field (name "MPN") "53047-0510"))
      (libsource (lib "eagle-import") (part "53?-05047"))
    )
    (comp (ref "I2C1_IR1")
      (value "53047-05")
      (footprint "eagle-import:53047-05")
      (fields (field (name "MF") "MOLEX") (field (name "MPN") "53047-0510"))
      (libsource (lib "eagle-import") (part "53?-05047"))
    )
    (comp (ref "I2C1_IR2")
      (value "53047-05")
      (footprint "eagle-import:53047-05")
      (fields (field (name "MF") "MOLEX") (field (name "MPN") "53047-0510"))
      (libsource (lib "eagle-import") (part "53?-05047"))
    )
    (comp (ref "I2C1_L1")
      (value "53047-05")
      (footprint "eagle-import:53047-05")
      (fields (field (name "MF") "MOLEX") (field (name "MPN") "53047-0510"))
      (libsource (lib "eagle-import") (part "53?-05047"))
    )
    (comp (ref "I2C1_L2")
      (value "53047-05")
      (footprint "eagle-import:53047-05")
      (fields (field (name "MF") "MOLEX") (field (name "MPN") "53047-0510"))
      (libsource (lib "eagle-import") (part "53?-05047"))
    )
    (comp (ref "I2C1_P")
      (value "53047-05")
      (footprint "eagle-import:53047-05")
      (fields (field (name "MF") "MOLEX") (field (name "MPN") "53047-0510"))
      (libsource (lib "eagle-import") (part "53?-05047"))
    )
    (comp (ref "I2C6_AIR")
      (value "53047-05")
      (footprint "eagle-import:53047-05")
      (fields (field (name "MF") "MOLEX") (field (name "MPN") "53047-0510"))
      (libsource (lib "eagle-import") (part "53?-05047"))
    )
    (comp (ref "I2C6_IR1")
      (value "53047-05")
      (footprint "eagle-import:53047-05")
      (fields (field (name "MF") "MOLEX") (field (name "MPN") "53047-0510"))
      (libsource (lib "eagle-import") (part "53?-05047"))
    )
    (comp (ref "I2C6_IR2")
      (value "53047-05")
      (footprint "eagle-import:53047-05")
      (fields (field (name "MF") "MOLEX") (field (name "MPN") "53047-0510"))
      (libsource (lib "eagle-import") (part "53?-05047"))
    )
    (comp (ref "I2C6_L1")
      (value "53047-05")
      (footprint "eagle-import:53047-05")
      (fields (field (name "MF") "MOLEX") (field (name "MPN") "53047-0510"))
      (libsource (lib "eagle-import") (part "53?-05047"))
    )
    (comp (ref "I2C6_L2")
      (value "53047-05")
      (footprint "eagle-import:53047-05")
      (fields (field (name "MF") "MOLEX") (field (name "MPN") "53047-0510"))
      (libsource (lib "eagle-import") (part "53?-05047"))
    )
    (comp (ref "E_1")
      (value "EDISON_CONNECTOR_SEGMENTED")
      (footprint "eagle-import:EDISON_DAUGHTER")
      (fields (field (name "MOUSER") " 798-DF40HC3070DS4V51 "))
      (libsource (lib "eagle-import") (part "EDISON_CONNECTOR_SEGMENTED"))
    )
    (comp (ref "JP3")
      (value "PINHD-1X3")
      (footprint "eagle-import:1X03")
      (libsource (lib "eagle-import") (part "PINHD-1X3"))
    )
    (comp (ref "JP5")
      (value "PINHD-1X2")
      (footprint "eagle-import:1X02")
      (libsource (lib "eagle-import") (part "PINHD-1X2"))
    )
    (comp (ref "R27")
      (value "220")
      (footprint "eagle-import:R0201")
      (libsource (lib "eagle-import") (part "R-EU_R0201"))
    )
    (comp (ref "R34")
      (value "10k")
      (footprint "eagle-import:R0201")
      (libsource (lib "eagle-import") (part "R-EU_R0201"))
    )
    (comp (ref "R35")
      (value "10k")
      (footprint "eagle-import:R0201")
      (libsource (lib "eagle-import") (part "R-EU_R0201"))
    )
    (comp (ref "U8")
      (value "EDISON_CONNECTOR_FULLHEADER")
      (footprint "eagle-import:DF40C-70DP-0.4(51)")
      (libsource (lib "eagle-import") (part "EDISON_CONNECTOR_FULLHEADER"))
    )
  )
  (nets
    (net (code "1") (name "5VUSB_FROM_SOCKET") (class "Default")
      (node (ref "1K") (pin "2") (pinfunction "2_2") (pintype "passive"))
      (node (ref "C10") (pin "1") (pinfunction "1_1") (pintype "passive"))
      (node (ref "C9") (pin "1") (pinfunction "1_1") (pintype "passive"))
      (node (ref "D1") (pin "A") (pinfunction "A_A") (pintype "passive"))
      (node (ref "JP2") (pin "1") (pinfunction "1_1") (pintype "passive"))
      (node (ref "R21") (pin "2") (pinfunction "2_2") (pintype "passive"))
      (node (ref "U$1") (pin "1") (pinfunction "VBUS_1") (pintype "power_in"))
      (node (ref "U3") (pin "13") (pinfunction "IN_13") (pintype "bidirectional"))
    )
    (net (code "2") (name "BATT+") (class "Default")
      (node (ref "BATT") (pin "1") (pinfunction "S_1") (pintype "passive"))
      (node (ref "C34") (pin "1") (pinfunction "1_1") (pintype "passive"))
      (node (ref "JP1") (pin "1") (pinfunction "1_1") (pintype "passive"))
      (node (ref "R3") (pin "2") (pinfunction "2_2") (pintype "passive"))
      (node (ref "U11") (pin "10") (pinfunction "SYNC/MODE_10") (pintype "bidirectional"))
      (node (ref "U11") (pin "11") (pinfunction "VSEL_11") (pintype "bidirectional"))
      (node (ref "U11") (pin "5") (pinfunction "PVIN_5") (pintype "bidirectional"))
      (node (ref "U11") (pin "7") (pinfunction "VDD_7") (pintype "bidirectional"))
      (node (ref "U3") (pin "2") (pinfunction "BAT_2") (pintype "bidirectional"))
      (node (ref "U3") (pin "3") (pinfunction "BAT_3") (pintype "bidirectional"))
    )
    (net (code "3") (name "CD") (class "Default")
      (node (ref "E_1") (pin "60") (pinfunction "GP77_SD_0_CD#_60") (pintype "bidirectional"))
      (node (ref "U7") (pin "CD1") (pinfunction "SHIELD_CD1") (pintype "bidirectional"))
      (node (ref "U8") (pin "60") (pinfunction "GP77_SD_0_CD#_60") (pintype "bidirectional"))
    )
    (net (code "4") (name "CLK") (class "Default")
      (node (ref "E_1") (pin "58") (pinfunction "GP78_SD_0_CLK_58") (pintype "bidirectional"))
      (node (ref "U8") (pin "58") (pinfunction "GP78_SD_0_CLK_58") (pintype "bidirectional"))
      (node (ref "U9") (pin "P$4") (pinfunction "A4_P$4") (pintype "bidirectional"))
    )
    (net (code "5") (name "CMD") (class "Default")
      (node (ref "E_1") (pin "62") (pinfunction "GP79_SD_0_CMD_62") (pintype "bidirectional"))
      (node (ref "U8") (pin "62") (pinfunction "GP79_SD_0_CMD_62") (pintype "bidirectional"))
      (node (ref "U9") (pin "P$3") (pinfunction "A3_P$3") (pintype "bidirectional"))
    )
    (net (code "6") (name "CTS1") (class "Default")
      (node (ref "E_1") (pin "65") (pinfunction "GP128_UART_1_CTS_65") (pintype "bidirectional"))
      (node (ref "U1") (pin "1") (pinfunction "A1_1") (pintype "bidirectional"))
      (node (ref "U8") (pin "65") (pinfunction "GP128_UART_1_CTS_65") (pintype "bidirectional"))
    )
    (net (code "7") (name "CTS1_HI") (class "Default")
      (node (ref "TP9") (pin "TP") (pinfunction "TP_TP") (pintype "input"))
      (node (ref "U1") (pin "20") (pinfunction "B1_20") (pintype "bidirectional"))
    )
    (net (code "8") (name "DAT0") (class "Default")
      (node (ref "E_1") (pin "66") (pinfunction "GP80_SD_0_DAT0_66") (pintype "bidirectional"))
      (node (ref "U8") (pin "66") (pinfunction "GP80_SD_0_DAT0_66") (pintype "bidirectional"))
      (node (ref "U9") (pin "P$7") (pinfunction "A5_P$7") (pintype "bidirectional"))
    )
    (net (code "9") (name "DAT1") (class "Default")
      (node (ref "E_1") (pin "70") (pinfunction "GP81_SD_0_DAT1_70") (pintype "bidirectional"))
      (node (ref "U8") (pin "70") (pinfunction "GP81_SD_0_DAT1_70") (pintype "bidirectional"))
      (node (ref "U9") (pin "P$8") (pinfunction "A6_P$8") (pintype "bidirectional"))
    )
    (net (code "10") (name "DAT2") (class "Default")
      (node (ref "E_1") (pin "64") (pinfunction "GP82_SD_0_DAT2_64") (pintype "bidirectional"))
      (node (ref "U8") (pin "64") (pinfunction "GP82_SD_0_DAT2_64") (pintype "bidirectional"))
      (node (ref "U9") (pin "P$1") (pinfunction "A1_P$1") (pintype "bidirectional"))
    )
    (net (code "11") (name "DAT3") (class "Default")
      (node (ref "E_1") (pin "68") (pinfunction "GP83_SD_0_DAT3_68") (pintype "bidirectional"))
      (node (ref "U8") (pin "68") (pinfunction "GP83_SD_0_DAT3_68") (pintype "bidirectional"))
      (node (ref "U9") (pin "P$2") (pinfunction "A2_P$2") (pintype "bidirectional"))
    )
    (net (code "12") (name "DN") (class "Default")
      (node (ref "E_1") (pin "18") (pinfunction "USB_DN_18") (pintype "bidirectional"))
      (node (ref "U$1") (pin "2") (pinfunction "D-_2") (pintype "bidirectional"))
      (node (ref "U8") (pin "18") (pinfunction "USB_DN_18") (pintype "bidirectional"))
    )
    (net (code "13") (name "DP") (class "Default")
      (node (ref "E_1") (pin "16") (pinfunction "USB_DP_16") (pintype "bidirectional"))
      (node (ref "U$1") (pin "3") (pinfunction "D+_3") (pintype "bidirectional"))
      (node (ref "U8") (pin "16") (pinfunction "USB_DP_16") (pintype "bidirectional"))
    )
    (net (code "14") (name "EIO0") (class "Default")
      (node (ref "3DPAD_1") (pin "1") (pinfunction "S_1") (pintype "passive"))
      (node (ref "U2") (pin "13") (pinfunction "B7_13") (pintype "bidirectional"))
    )
    (net (code "15") (name "EIO1") (class "Default")
      (node (ref "3DPAD_2") (pin "5") (pinfunction "S_5") (pintype "passive"))
      (node (ref "U2") (pin "20") (pinfunction "B1_20") (pintype "bidirectional"))
    )
    (net (code "16") (name "EIO2") (class "Default")
      (node (ref "3DPAD_2") (pin "6") (pinfunction "S_6") (pintype "passive"))
      (node (ref "U2") (pin "18") (pinfunction "B2_18") (pintype "bidirectional"))
    )
    (net (code "17") (name "EIO3") (class "Default")
      (node (ref "3DPAD_2") (pin "4") (pinfunction "S_4") (pintype "passive"))
      (node (ref "U2") (pin "17") (pinfunction "B3_17") (pintype "bidirectional"))
    )
    (net (code "18") (name "EIO6") (class "Default")
      (node (ref "3DPAD_2") (pin "3") (pinfunction "S_3") (pintype "passive"))
      (node (ref "U2") (pin "16") (pinfunction "B4_16") (pintype "bidirectional"))
    )
    (net (code "19") (name "EIO7") (class "Default")
      (node (ref "3DPAD_2") (pin "2") (pinfunction "S_2") (pintype "passive"))
      (node (ref "U2") (pin "15") (pinfunction "B5_15") (pintype "bidirectional"))
    )
    (net (code "20") (name "FAULT") (class "Default")
      (node (ref "E_1") (pin "19") (pinfunction "FAULT_19") (pintype "bidirectional"))
      (node (ref "R31") (pin "2") (pinfunction "2_2") (pintype "passive"))
      (node (ref "U4") (pin "4") (pinfunction "FAULT_4") (pintype "bidirectional"))
      (node (ref "U8") (pin "19") (pinfunction "FAULT_19") (pintype "bidirectional"))
    )
    (net (code "21") (name "FB") (class "Default")
      (node (ref "E_1") (pin "44") (pinfunction "GP84_SD_0_CLK_FB_44") (pintype "bidirectional"))
      (node (ref "U8") (pin "44") (pinfunction "GP84_SD_CLK_FB_44") (pintype "bidirectional"))
      (node (ref "U9") (pin "P$9") (pinfunction "A7_P$9") (pintype "bidirectional"))
    )
    (net (code "22") (name "FW_RCVR") (class "Default")
      (node (ref "E_1") (pin "69") (pinfunction "FW_RCVR_69") (pintype "bidirectional"))
      (node (ref "R35") (pin "1") (pinfunction "1_1") (pintype "passive"))
      (node (ref "U1") (pin "4") (pinfunction "A3_4") (pintype "bidirectional"))
      (node (ref "U8") (pin "69") (pinfunction "FW_RCVR_69") (pintype "bidirectional"))
    )
    (net (code "23") (name "FW_RCVR_5V") (class "Default")
      (node (ref "R32") (pin "1") (pinfunction "1_1") (pintype "passive"))
      (node (ref "U1") (pin "17") (pinfunction "B3_17") (pintype "bidirectional"))
      (node (ref "U5") (pin "8") (pinfunction "RC6/AN8/~{SS/T13CKI/T1OSCI}_8") (pintype "bidirectional"))
    )
    (net (code "24") (name "GND") (class "Default")
      (node (ref "3DPAD_1") (pin "2") (pinfunction "S_2") (pintype "passive"))
      (node (ref "3DPAD_2") (pin "1") (pinfunction "S_1") (pintype "passive"))
      (node (ref "BATT") (pin "2") (pinfunction "S_2") (pintype "passive"))
      (node (ref "C1") (pin "2") (pinfunction "2_2") (pintype "passive"))
      (node (ref "C10") (pin "2") (pinfunction "2_2") (pintype "passive"))
      (node (ref "C11") (pin "2") (pinfunction "2_2") (pintype "passive"))
      (node (ref "C12") (pin "2") (pinfunction "2_2") (pintype "passive"))
      (node (ref "C13") (pin "2") (pinfunction "2_2") (pintype "passive"))
      (node (ref "C14") (pin "2") (pinfunction "2_2") (pintype "passive"))
      (node (ref "C15") (pin "2") (pinfunction "2_2") (pintype "passive"))
      (node (ref "C16") (pin "1") (pinfunction "1_1") (pintype "passive"))
      (node (ref "C17") (pin "2") (pinfunction "2_2") (pintype "passive"))
      (node (ref "C18") (pin "2") (pinfunction "2_2") (pintype "passive"))
      (node (ref "C19") (pin "2") (pinfunction "2_2") (pintype "passive"))
      (node (ref "C2") (pin "2") (pinfunction "2_2") (pintype "passive"))
      (node (ref "C20") (pin "2") (pinfunction "2_2") (pintype "passive"))
      (node (ref "C21") (pin "2") (pinfunction "2_2") (pintype "passive"))
      (node (ref "C22") (pin "2") (pinfunction "2_2") (pintype "passive"))
      (node (ref "C23") (pin "2") (pinfunction "2_2") (pintype "passive"))
      (node (ref "C24") (pin "1") (pinfunction "1_1") (pintype "passive"))
      (node (ref "C25") (pin "1") (pinfunction "1_1") (pintype "passive"))
      (node (ref "C26") (pin "2") (pinfunction "2_2") (pintype "passive"))
      (node (ref "C27") (pin "2") (pinfunction "2_2") (pintype "passive"))
      (node (ref "C28") (pin "2") (pinfunction "2_2") (pintype "passive"))
      (node (ref "C29") (pin "2") (pinfunction "2_2") (pintype "passive"))
      (node (ref "C3") (pin "2") (pinfunction "2_2") (pintype "passive"))
      (node (ref "C30") (pin "2") (pinfunction "2_2") (pintype "passive"))
      (node (ref "C31") (pin "2") (pinfunction "2_2") (pintype "passive"))
      (node (ref "C32") (pin "2") (pinfunction "2_2") (pintype "passive"))
      (node (ref "C33") (pin "2") (pinfunction "2_2") (pintype "passive"))
      (node (ref "C34") (pin "2") (pinfunction "2_2") (pintype "passive"))
      (node (ref "C35") (pin "2") (pinfunction "2_2") (pintype "passive"))
      (node (ref "C36") (pin "1") (pinfunction "1_1") (pintype "passive"))
      (node (ref "C37") (pin "1") (pinfunction "1_1") (pintype "passive"))
      (node (ref "C38") (pin "1") (pinfunction "1_1") (pintype "passive"))
      (node (ref "C39") (pin "1") (pinfunction "1_1") (pintype "passive"))
      (node (ref "C4") (pin "2") (pinfunction "2_2") (pintype "passive"))
      (node (ref "C40") (pin "1") (pinfunction "1_1") (pintype "passive"))
      (node (ref "C41") (pin "1") (pinfunction "1_1") (pintype "passive"))
      (node (ref "C42") (pin "2") (pinfunction "2_2") (pintype "passive"))
      (node (ref "C43") (pin "2") (pinfunction "2_2") (pintype "passive"))
      (node (ref "C5") (pin "2") (pinfunction "2_2") (pintype "passive"))
      (node (ref "C6") (pin "2") (pinfunction "2_2") (pintype "passive"))
      (node (ref "C7") (pin "2") (pinfunction "2_2") (pintype "passive"))
      (node (ref "C8") (pin "2") (pinfunction "2_2") (pintype "passive"))
      (node (ref "C9") (pin "2") (pinfunction "2_2") (pintype "passive"))
      (node (ref "E_1") (pin "1") (pinfunction "GND_1") (pintype "bidirectional"))
      (node (ref "E_1") (pin "11") (pinfunction "GND_11") (pintype "bidirectional"))
      (node (ref "E_1") (pin "13") (pinfunction "GND_13") (pintype "bidirectional"))
      (node (ref "E_1") (pin "15") (pinfunction "GND_15") (pintype "bidirectional"))
      (node (ref "E_1") (pin "5") (pinfunction "GND_5") (pintype "bidirectional"))
      (node (ref "E_1") (pin "9") (pinfunction "GND_9") (pintype "bidirectional"))
      (node (ref "I2C1_ACC") (pin "2") (pinfunction "S_2") (pintype "passive"))
      (node (ref "I2C1_H") (pin "2") (pinfunction "S_2") (pintype "passive"))
      (node (ref "I2C1_IR1") (pin "2") (pinfunction "S_2") (pintype "passive"))
      (node (ref "I2C1_IR2") (pin "2") (pinfunction "S_2") (pintype "passive"))
      (node (ref "I2C1_L1") (pin "2") (pinfunction "S_2") (pintype "passive"))
      (node (ref "I2C1_L2") (pin "2") (pinfunction "S_2") (pintype "passive"))
      (node (ref "I2C1_P") (pin "2") (pinfunction "S_2") (pintype "passive"))
      (node (ref "I2C6_AIR") (pin "2") (pinfunction "S_2") (pintype "passive"))
      (node (ref "I2C6_IR1") (pin "2") (pinfunction "S_2") (pintype "passive"))
      (node (ref "I2C6_IR2") (pin "2") (pinfunction "S_2") (pintype "passive"))
      (node (ref "I2C6_L1") (pin "2") (pinfunction "S_2") (pintype "passive"))
      (node (ref "I2C6_L2") (pin "2") (pinfunction "S_2") (pintype "passive"))
      (node (ref "ICSP") (pin "3") (pinfunction "S_3") (pintype "passive"))
      (node (ref "JP1") (pin "2") (pinfunction "2_2") (pintype "passive"))
      (node (ref "JP2") (pin "2") (pinfunction "2_2") (pintype "passive"))
      (node (ref "JP5") (pin "1") (pinfunction "1_1") (pintype "passive"))
      (node (ref "JP5") (pin "2") (pinfunction "2_2") (pintype "passive"))
      (node (ref "LED2") (pin "C") (pinfunction "C_C") (pintype "passive"))
      (node (ref "LED3") (pin "C") (pinfunction "C_C") (pintype "passive"))
      (node (ref "Q1") (pin "2") (pinfunction "S_2") (pintype "passive"))
      (node (ref "Q2") (pin "2") (pinfunction "S_2") (pintype "passive"))
      (node (ref "Q3") (pin "2") (pinfunction "S_2") (pintype "passive"))
      (node (ref "Q4") (pin "2") (pinfunction "S_2") (pintype "passive"))
      (node (ref "R11") (pin "1") (pinfunction "1_1") (pintype "passive"))
      (node (ref "R12") (pin "1") (pinfunction "1_1") (pintype "passive"))
      (node (ref "R13") (pin "1") (pinfunction "1_1") (pintype "passive"))
      (node (ref "R14") (pin "1") (pinfunction "1_1") (pintype "passive"))
      (node (ref "R17") (pin "2") (pinfunction "2_2") (pintype "passive"))
      (node (ref "R18") (pin "1") (pinfunction "1_1") (pintype "passive"))
      (node (ref "R23") (pin "2") (pinfunction "2_2") (pintype "passive"))
      (node (ref "R30") (pin "2") (pinfunction "2_2") (pintype "passive"))
      (node (ref "R32") (pin "2") (pinfunction "2_2") (pintype "passive"))
      (node (ref "R33") (pin "2") (pinfunction "2_2") (pintype "passive"))
      (node (ref "R34") (pin "2") (pinfunction "2_2") (pintype "passive"))
      (node (ref "R35") (pin "2") (pinfunction "2_2") (pintype "passive"))
      (node (ref "S1") (pin "1") (pinfunction "1_1") (pintype "passive"))
      (node (ref "SJ1") (pin "1") (pinfunction "1_1") (pintype "passive"))
      (node (ref "U$1") (pin "5") (pinfunction "GND_5") (pintype "power_in"))
      (node (ref "U$3") (pin "2") (pinfunction "2_2") (pintype "passive"))
      (node (ref "U1") (pin "11") (pinfunction "GND_11") (pintype "bidirectional"))
      (node (ref "U11") (pin "3") (pinfunction "PGND_3") (pintype "bidirectional"))
      (node (ref "U11") (pin "8") (pinfunction "SGND_8") (pintype "bidirectional"))
      (node (ref "U11") (pin "9") (pinfunction "SGND_9") (pintype "bidirectional"))
      (node (ref "U11") (pin "PAD") (pinfunction "SGND_PAD") (pintype "bidirectional"))
      (node (ref "U12") (pin "4") (pinfunction "GND_4") (pintype "bidirectional"))
      (node (ref "U15") (pin "4") (pinfunction "GND_4") (pintype "bidirectional"))
      (node (ref "U16") (pin "4") (pinfunction "GND_4") (pintype "bidirectional"))
      (node (ref "U2") (pin "11") (pinfunction "GND_11") (pintype "bidirectional"))
      (node (ref "U3") (pin "4") (pinfunction "~{CE}_4") (pintype "bidirectional"))
      (node (ref "U3") (pin "6") (pinfunction "EN1_6") (pintype "bidirectional"))
      (node (ref "U3") (pin "8") (pinfunction "VSS_8") (pintype "bidirectional"))
      (node (ref "U3") (pin "PAD0") (pinfunction "VSS_PAD0") (pintype "bidirectional"))
      (node (ref "U3") (pin "PAD1") (pinfunction "VSS_PAD1") (pintype "bidirectional"))
      (node (ref "U4") (pin "2") (pinfunction "GND_2") (pintype "bidirectional"))
      (node (ref "U5") (pin "20") (pinfunction "VSS_20") (pintype "power_in"))
      (node (ref "U6") (pin "4") (pinfunction "GND_4") (pintype "bidirectional"))
      (node (ref "U7") (pin "6") (pinfunction "GND_6") (pintype "bidirectional"))
      (node (ref "U7") (pin "GND1") (pinfunction "SHIELD_GND1") (pintype "bidirectional"))
      (node (ref "U7") (pin "GND3") (pinfunction "SHIELD_GND3") (pintype "bidirectional"))
      (node (ref "U8") (pin "1") (pinfunction "GND_1") (pintype "bidirectional"))
      (node (ref "U8") (pin "11") (pinfunction "GND_11") (pintype "bidirectional"))
      (node (ref "U8") (pin "13") (pinfunction "GND_13") (pintype "bidirectional"))
      (node (ref "U8") (pin "15") (pinfunction "GND_15") (pintype "bidirectional"))
      (node (ref "U8") (pin "5") (pinfunction "GND_5") (pintype "bidirectional"))
      (node (ref "U8") (pin "9") (pinfunction "GND_9") (pintype "bidirectional"))
      (node (ref "U9") (pin "P$15") (pinfunction "GND_P$15") (pintype "bidirectional"))
    )
    (net (code "25") (name "GP15") (class "Default")
      (node (ref "E_1") (pin "42") (pinfunction "GP15_42") (pintype "bidirectional"))
      (node (ref "U8") (pin "42") (pinfunction "GP15_42") (pintype "bidirectional"))
    )
    (net (code "26") (name "GP40") (class "Default")
      (node (ref "E_1") (pin "52") (pinfunction "GP40_I2S_2_CLK_52") (pintype "bidirectional"))
      (node (ref "U8") (pin "52") (pinfunction "GP40_I2S_2_CLK_52") (pintype "bidirectional"))
    )
    (net (code "27") (name "GP41") (class "Default")
      (node (ref "E_1") (pin "54") (pinfunction "GP41_I2S_2_FS_54") (pintype "bidirectional"))
      (node (ref "U8") (pin "54") (pinfunction "GP41_I2S_2_FS_54") (pintype "bidirectional"))
    )
    (net (code "28") (name "GP42") (class "Default")
      (node (ref "E_1") (pin "50") (pinfunction "GP42_I2S_2_RXD_50") (pintype "bidirectional"))
      (node (ref "U8") (pin "50") (pinfunction "GP42_I2S_2_RXD_50") (pintype "bidirectional"))
    )
    (net (code "29") (name "GP43") (class "Default")
      (node (ref "E_1") (pin "56") (pinfunction "GP43_I2S_2_TXD_56") (pintype "bidirectional"))
      (node (ref "U8") (pin "56") (pinfunction "GP43_I2S_2_TXD_56") (pintype "bidirectional"))
    )
    (net (code "30") (name "GP44") (class "Default")
      (node (ref "E_1") (pin "24") (pinfunction "GP44_24") (pintype "bidirectional"))
      (node (ref "U2") (pin "6") (pinfunction "A5_6") (pintype "bidirectional"))
      (node (ref "U8") (pin "24") (pinfunction "GP44_24") (pintype "bidirectional"))
    )
    (net (code "31") (name "GP45") (class "Default")
      (node (ref "E_1") (pin "26") (pinfunction "GP45_26") (pintype "bidirectional"))
      (node (ref "U2") (pin "8") (pinfunction "A7_8") (pintype "bidirectional"))
      (node (ref "U8") (pin "26") (pinfunction "GP45_26") (pintype "bidirectional"))
    )
    (net (code "32") (name "GP46") (class "Default")
      (node (ref "E_1") (pin "28") (pinfunction "GP46_28") (pintype "bidirectional"))
      (node (ref "U2") (pin "9") (pinfunction "A8_9") (pintype "bidirectional"))
      (node (ref "U8") (pin "28") (pinfunction "GP46_28") (pintype "bidirectional"))
    )
    (net (code "33") (name "GP46_HI") (class "Default")
      (node (ref "I2C6_AIR") (pin "3") (pinfunction "S_3") (pintype "passive"))
      (node (ref "U2") (pin "12") (pinfunction "B8_12") (pintype "bidirectional"))
    )
    (net (code "34") (name "GP47") (class "Default")
      (node (ref "E_1") (pin "30") (pinfunction "GP47_30") (pintype "bidirectional"))
      (node (ref "U8") (pin "30") (pinfunction "GP47_30") (pintype "bidirectional"))
    )
    (net (code "35") (name "GP48") (class "Default")
      (node (ref "E_1") (pin "32") (pinfunction "GP48_32") (pintype "bidirectional"))
      (node (ref "U2") (pin "4") (pinfunction "A3_4") (pintype "bidirectional"))
      (node (ref "U8") (pin "32") (pinfunction "GP48_32") (pintype "bidirectional"))
    )
    (net (code "36") (name "GP49") (class "Default")
      (node (ref "E_1") (pin "34") (pinfunction "GP49_34") (pintype "bidirectional"))
      (node (ref "U2") (pin "5") (pinfunction "A4_5") (pintype "bidirectional"))
      (node (ref "U8") (pin "34") (pinfunction "GP49_34") (pintype "bidirectional"))
    )
    (net (code "37") (name "GP109") (class "Default")
      (node (ref "E_1") (pin "55") (pinfunction "GP109_SPI_2_CLK_55") (pintype "bidirectional"))
      (node (ref "U8") (pin "55") (pinfunction "GP109_SPI_2_CLK_55") (pintype "bidirectional"))
    )
    (net (code "38") (name "GP110") (class "Default")
      (node (ref "E_1") (pin "53") (pinfunction "GP110_SPI_2_FS0_53") (pintype "bidirectional"))
      (node (ref "U8") (pin "53") (pinfunction "GP110_SPI_2_FS0_53") (pintype "bidirectional"))
    )
    (net (code "39") (name "GP111") (class "Default")
      (node (ref "E_1") (pin "51") (pinfunction "GP111_SPI_2_FS1_51") (pintype "bidirectional"))
      (node (ref "U8") (pin "51") (pinfunction "GP111_SPI_2_FS1_51") (pintype "bidirectional"))
    )
    (net (code "40") (name "GP114") (class "Default")
      (node (ref "E_1") (pin "59") (pinfunction "GP114_SPI_2_RXD_59") (pintype "bidirectional"))
      (node (ref "U8") (pin "59") (pinfunction "GP114_SPI_2_RXD_59") (pintype "bidirectional"))
    )
    (net (code "41") (name "GP115") (class "Default")
      (node (ref "E_1") (pin "57") (pinfunction "GP115_SPI_2_TXD_57") (pintype "bidirectional"))
      (node (ref "U8") (pin "57") (pinfunction "GP115_SPI_2_TXD_57") (pintype "bidirectional"))
    )
    (net (code "42") (name "GP165") (class "Default")
      (node (ref "E_1") (pin "25") (pinfunction "GP165_25") (pintype "bidirectional"))
      (node (ref "U2") (pin "7") (pinfunction "A6_7") (pintype "bidirectional"))
      (node (ref "U8") (pin "25") (pinfunction "GP165_25") (pintype "bidirectional"))
    )
    (net (code "43") (name "ID") (class "Default")
      (node (ref "E_1") (pin "3") (pinfunction "USB_ID_3") (pintype "bidirectional"))
      (node (ref "U$1") (pin "4") (pinfunction "ID_4") (pintype "bidirectional"))
      (node (ref "U8") (pin "3") (pinfunction "USB_ID_3") (pintype "bidirectional"))
    )
    (net (code "44") (name "MCLR_3D") (class "Default")
      (node (ref "3DPAD_1") (pin "4") (pinfunction "S_4") (pintype "passive"))
      (node (ref "U2") (pin "14") (pinfunction "B6_14") (pintype "bidirectional"))
    )
    (net (code "45") (name "MCLR_UC") (class "Default")
      (node (ref "E_1") (pin "48") (pinfunction "GP14_48") (pintype "bidirectional"))
      (node (ref "Q1") (pin "1") (pinfunction "G_1") (pintype "passive"))
      (node (ref "R23") (pin "1") (pinfunction "1_1") (pintype "passive"))
      (node (ref "U8") (pin "48") (pinfunction "GP14_48") (pintype "bidirectional"))
    )
    (net (code "46") (name "MCLR_UC_5V") (class "Default")
      (node (ref "D2") (pin "A") (pinfunction "A_A") (pintype "passive"))
      (node (ref "R24") (pin "2") (pinfunction "2_2") (pintype "passive"))
    )
    (net (code "47") (name "MSIC") (class "Default")
      (node (ref "E_1") (pin "7") (pinfunction "MSIC_SLP_CLK_7") (pintype "bidirectional"))
      (node (ref "U8") (pin "7") (pinfunction "MSIC_SLP_CLK_7") (pintype "bidirectional"))
    )
    (net (code "48") (name "N$20") (class "Default")
      (node (ref "U7") (pin "1") (pinfunction "NC_1") (pintype "bidirectional"))
      (node (ref "U9") (pin "P$20") (pinfunction "B1_P$20") (pintype "bidirectional"))
    )
    (net (code "49") (name "N$21") (class "Default")
      (node (ref "U7") (pin "2") (pinfunction "CS_2") (pintype "bidirectional"))
      (node (ref "U9") (pin "P$19") (pinfunction "B2_P$19") (pintype "bidirectional"))
    )
    (net (code "50") (name "N$22") (class "Default")
      (node (ref "U7") (pin "3") (pinfunction "DI_3") (pintype "bidirectional"))
      (node (ref "U9") (pin "P$18") (pinfunction "B3_P$18") (pintype "bidirectional"))
    )
    (net (code "51") (name "N$23") (class "Default")
      (node (ref "U7") (pin "7") (pinfunction "DO_7") (pintype "bidirectional"))
      (node (ref "U9") (pin "P$14") (pinfunction "B5_P$14") (pintype "bidirectional"))
    )
    (net (code "52") (name "N$24") (class "Default")
      (node (ref "U7") (pin "8") (pinfunction "RSV_8") (pintype "bidirectional"))
      (node (ref "U9") (pin "P$13") (pinfunction "B6_P$13") (pintype "bidirectional"))
    )
    (net (code "53") (name "Net-(LED1-PadA)") (class "Default")
      (node (ref "LED1") (pin "A") (pinfunction "A_A") (pintype "passive"))
      (node (ref "R16") (pin "2") (pinfunction "2_2") (pintype "passive"))
    )
    (net (code "54") (name "Net-(LED2-PadA)") (class "Default")
      (node (ref "LED2") (pin "A") (pinfunction "A_A") (pintype "passive"))
      (node (ref "R21") (pin "1") (pinfunction "1_1") (pintype "passive"))
    )
    (net (code "55") (name "Net-(LED3-PadA)") (class "Default")
      (node (ref "LED3") (pin "A") (pinfunction "A_A") (pintype "passive"))
      (node (ref "R38") (pin "1") (pinfunction "1_1") (pintype "passive"))
    )
    (net (code "56") (name "Net-(Q1-D)") (class "Default")
      (node (ref "Q1") (pin "3") (pinfunction "D_3") (pintype "passive"))
      (node (ref "R24") (pin "1") (pinfunction "1_1") (pintype "passive"))
      (node (ref "R37") (pin "1") (pinfunction "1_1") (pintype "passive"))
    )
    (net (code "57") (name "Net-(Q4-D)") (class "Default")
      (node (ref "Q4") (pin "3") (pinfunction "D_3") (pintype "passive"))
      (node (ref "R3") (pin "1") (pinfunction "1_1") (pintype "passive"))
      (node (ref "U11") (pin "6") (pinfunction "EN_6") (pintype "bidirectional"))
    )
    (net (code "58") (name "Net-(Q4-G)") (class "Default")
      (node (ref "1K") (pin "1") (pinfunction "1_1") (pintype "passive"))
      (node (ref "Q4") (pin "1") (pinfunction "G_1") (pintype "passive"))
    )
    (net (code "59") (name "Net-(R15-Pad1)") (class "Default")
      (node (ref "R15") (pin "1") (pinfunction "1_1") (pintype "passive"))
      (node (ref "SJ1") (pin "2") (pinfunction "2_2") (pintype "passive"))
    )
    (net (code "60") (name "Net-(S1-2)") (class "Default")
      (node (ref "R41") (pin "2") (pinfunction "2_2") (pintype "passive"))
      (node (ref "S1") (pin "3") (pinfunction "2_3") (pintype "passive"))
      (node (ref "U5") (pin "15") (pinfunction "RC1/AN5/C12IN1-/INT1/VREF-_15") (pintype "bidirectional"))
    )
    (net (code "61") (name "Net-(U3-ILM)") (class "Default")
      (node (ref "R12") (pin "2") (pinfunction "2_2") (pintype "passive"))
      (node (ref "U3") (pin "12") (pinfunction "ILM_12") (pintype "bidirectional"))
    )
    (net (code "62") (name "Net-(U3-ISET)") (class "Default")
      (node (ref "R13") (pin "2") (pinfunction "2_2") (pintype "passive"))
      (node (ref "U3") (pin "16") (pinfunction "ISET_16") (pintype "bidirectional"))
    )
    (net (code "63") (name "Net-(U3-ITERM)") (class "Default")
      (node (ref "R11") (pin "2") (pinfunction "2_2") (pintype "passive"))
      (node (ref "U3") (pin "15") (pinfunction "ITERM_15") (pintype "bidirectional"))
    )
    (net (code "64") (name "Net-(U3-TMR)") (class "Default")
      (node (ref "R14") (pin "2") (pinfunction "2_2") (pintype "passive"))
      (node (ref "U3") (pin "14") (pinfunction "TMR_14") (pintype "bidirectional"))
    )
    (net (code "65") (name "Net-(U3-TS)") (class "Default")
      (node (ref "JP1") (pin "3") (pinfunction "3_3") (pintype "passive"))
      (node (ref "R15") (pin "2") (pinfunction "2_2") (pintype "passive"))
      (node (ref "U3") (pin "1") (pinfunction "TS_1") (pintype "bidirectional"))
    )
    (net (code "66") (name "Net-(U3-~{CHG})") (class "Default")
      (node (ref "LED1") (pin "C") (pinfunction "C_C") (pintype "passive"))
      (node (ref "U3") (pin "9") (pinfunction "~{CHG}_9") (pintype "bidirectional"))
    )
    (net (code "67") (name "Net-(U4-ILIMIT)") (class "Default")
      (node (ref "R17") (pin "1") (pinfunction "1_1") (pintype "passive"))
      (node (ref "U4") (pin "5") (pinfunction "ILIMIT_5") (pintype "bidirectional"))
    )
    (net (code "68") (name "Net-(U5-RA4{slash}AN3{slash}OSC2{slash}CLKOUT)") (class "Default")
      (node (ref "U$3") (pin "3") (pinfunction "3_3") (pintype "passive"))
      (node (ref "U5") (pin "3") (pinfunction "RA4/AN3/OSC2/CLKOUT_3") (pintype "bidirectional"))
    )
    (net (code "69") (name "Net-(U5-RA5{slash}OSC1{slash}CLKIN)") (class "Default")
      (node (ref "U$3") (pin "1") (pinfunction "1_1") (pintype "passive"))
      (node (ref "U5") (pin "2") (pinfunction "RA5/OSC1/CLKIN_2") (pintype "bidirectional"))
    )
    (net (code "70") (name "Net-(U5-RC0{slash}AN4{slash}C12IN+{slash}INT0{slash}VREF+)") (class "Default")
      (node (ref "R38") (pin "2") (pinfunction "2_2") (pintype "passive"))
      (node (ref "U5") (pin "16") (pinfunction "RC0/AN4/C12IN+/INT0/VREF+_16") (pintype "bidirectional"))
    )
    (net (code "71") (name "Net-(U11-SW1)") (class "Default")
      (node (ref "L1") (pin "1") (pinfunction "1_1") (pintype "passive"))
      (node (ref "U11") (pin "4") (pinfunction "SW1_4") (pintype "bidirectional"))
    )
    (net (code "72") (name "Net-(U11-SW2)") (class "Default")
      (node (ref "L1") (pin "2") (pinfunction "2_2") (pintype "passive"))
      (node (ref "U11") (pin "2") (pinfunction "SW2_2") (pintype "bidirectional"))
    )
    (net (code "73") (name "OSC_CLK_OUT") (class "Default")
      (node (ref "E_1") (pin "67") (pinfunction "OSC_CLK_OUT_0_67") (pintype "bidirectional"))
      (node (ref "U8") (pin "67") (pinfunction "OSC_CLK_OUT_0_67") (pintype "bidirectional"))
    )
    (net (code "74") (name "PGC") (class "Default")
      (node (ref "ICSP") (pin "4") (pinfunction "S_4") (pintype "passive"))
      (node (ref "U5") (pin "18") (pinfunction "RA1/D-/PGC_18") (pintype "bidirectional"))
    )
    (net (code "75") (name "PGD") (class "Default")
      (node (ref "ICSP") (pin "5") (pinfunction "S_5") (pintype "passive"))
      (node (ref "U5") (pin "19") (pinfunction "RA0/D+/PGD_19") (pintype "bidirectional"))
    )
    (net (code "76") (name "PROG") (class "Default")
      (node (ref "D2") (pin "C") (pinfunction "C_C") (pintype "passive"))
      (node (ref "ICSP") (pin "2") (pinfunction "S_2") (pintype "passive"))
      (node (ref "U5") (pin "4") (pinfunction "RA3/~{MCLR/VPP}_4") (pintype "input"))
    )
    (net (code "77") (name "PSW") (class "Default")
      (node (ref "E_1") (pin "21") (pinfunction "PSW_21") (pintype "bidirectional"))
      (node (ref "R18") (pin "2") (pinfunction "2_2") (pintype "passive"))
      (node (ref "U4") (pin "3") (pinfunction "EN_3") (pintype "bidirectional"))
      (node (ref "U8") (pin "21") (pinfunction "PSW_21") (pintype "bidirectional"))
    )
    (net (code "78") (name "PWM0") (class "Default")
      (node (ref "E_1") (pin "35") (pinfunction "GP12_PWM0_35") (pintype "bidirectional"))
      (node (ref "U2") (pin "1") (pinfunction "A1_1") (pintype "bidirectional"))
      (node (ref "U8") (pin "35") (pinfunction "GP12_PWM0_35") (pintype "bidirectional"))
    )
    (net (code "79") (name "PWM1") (class "Default")
      (node (ref "E_1") (pin "33") (pinfunction "GP13_PWM1_33") (pintype "bidirectional"))
      (node (ref "U2") (pin "3") (pinfunction "A2_3") (pintype "bidirectional"))
      (node (ref "U8") (pin "33") (pinfunction "GP13_PWM1_33") (pintype "bidirectional"))
    )
    (net (code "80") (name "PWM2") (class "Default")
      (node (ref "E_1") (pin "37") (pinfunction "GP182_PWM2_37") (pintype "bidirectional"))
      (node (ref "U8") (pin "37") (pinfunction "GP182_PWM2_37") (pintype "bidirectional"))
    )
    (net (code "81") (name "PWM3") (class "Default")
      (node (ref "E_1") (pin "39") (pinfunction "GP183_PWM3_39") (pintype "bidirectional"))
      (node (ref "U8") (pin "39") (pinfunction "GP183_PWM3_39") (pintype "bidirectional"))
    )
    (net (code "82") (name "PWRBTN") (class "Default")
      (node (ref "E_1") (pin "17") (pinfunction "PWRBTN#_17") (pintype "bidirectional"))
      (node (ref "R27") (pin "1") (pinfunction "1_1") (pintype "passive"))
      (node (ref "U8") (pin "17") (pinfunction "PWRBTN#_17") (pintype "bidirectional"))
    )
    (net (code "83") (name "PWRBTN_5V") (class "Default")
      (node (ref "Q2") (pin "1") (pinfunction "G_1") (pintype "passive"))
      (node (ref "R30") (pin "1") (pinfunction "1_1") (pintype "passive"))
      (node (ref "U5") (pin "5") (pinfunction "RC5/CCP1/P1A/T0CKI_5") (pintype "bidirectional"))
    )
    (net (code "84") (name "PWRBTN_SIG") (class "Default")
      (node (ref "Q2") (pin "3") (pinfunction "D_3") (pintype "passive"))
      (node (ref "R22") (pin "2") (pinfunction "2_2") (pintype "passive"))
      (node (ref "R27") (pin "2") (pinfunction "2_2") (pintype "passive"))
    )
    (net (code "85") (name "RCVR_MODE") (class "Default")
      (node (ref "E_1") (pin "31") (pinfunction "RCVR_MODE_31") (pintype "bidirectional"))
      (node (ref "R34") (pin "1") (pinfunction "1_1") (pintype "passive"))
      (node (ref "U1") (pin "5") (pinfunction "A4_5") (pintype "bidirectional"))
      (node (ref "U8") (pin "31") (pinfunction "RCVR_MODE_31") (pintype "bidirectional"))
    )
    (net (code "86") (name "RCVR_MODE_5V") (class "Default")
      (node (ref "R33") (pin "1") (pinfunction "1_1") (pintype "passive"))
      (node (ref "U1") (pin "16") (pinfunction "B4_16") (pintype "bidirectional"))
      (node (ref "U5") (pin "7") (pinfunction "RC3/AN7/P1C/C12IN3-/PGM_7") (pintype "bidirectional"))
    )
    (net (code "87") (name "RESET") (class "Default")
      (node (ref "Q3") (pin "3") (pinfunction "D_3") (pintype "passive"))
      (node (ref "R28") (pin "2") (pinfunction "2_2") (pintype "passive"))
      (node (ref "R36") (pin "1") (pinfunction "1_1") (pintype "passive"))
    )
    (net (code "88") (name "RESET_OUT") (class "Default")
      (node (ref "E_1") (pin "36") (pinfunction "RESET_OUT#_36") (pintype "bidirectional"))
      (node (ref "Q3") (pin "1") (pinfunction "G_1") (pintype "passive"))
      (node (ref "R29") (pin "2") (pinfunction "2_2") (pintype "passive"))
      (node (ref "U8") (pin "36") (pinfunction "RESET_OUT#_36") (pintype "bidirectional"))
    )
    (net (code "89") (name "RESET_OUT_FLAG") (class "Default")
      (node (ref "R36") (pin "2") (pinfunction "2_2") (pintype "passive"))
      (node (ref "U5") (pin "6") (pinfunction "RC4/P1B/C12OUT/SRQ_6") (pintype "bidirectional"))
    )
    (net (code "90") (name "RTS1") (class "Default")
      (node (ref "E_1") (pin "63") (pinfunction "GP129_UART_1_RTS_63") (pintype "bidirectional"))
      (node (ref "U1") (pin "3") (pinfunction "A2_3") (pintype "bidirectional"))
      (node (ref "U8") (pin "63") (pinfunction "GP129_UART_1_RTS_63") (pintype "bidirectional"))
    )
    (net (code "91") (name "RTS1_HI") (class "Default")
      (node (ref "TP10") (pin "TP") (pinfunction "TP_TP") (pintype "input"))
      (node (ref "U1") (pin "18") (pinfunction "B2_18") (pintype "bidirectional"))
    )
    (net (code "92") (name "RX1") (class "Default")
      (node (ref "E_1") (pin "61") (pinfunction "GP130_UART_1_RX_61") (pintype "bidirectional"))
      (node (ref "U1") (pin "9") (pinfunction "A8_9") (pintype "bidirectional"))
      (node (ref "U8") (pin "61") (pinfunction "GP130_UART_1_RX_61") (pintype "bidirectional"))
    )
    (net (code "93") (name "RX1_HI") (class "Default")
      (node (ref "TP12") (pin "TP") (pinfunction "TP_TP") (pintype "input"))
      (node (ref "U1") (pin "12") (pinfunction "B8_12") (pintype "bidirectional"))
    )
    (net (code "94") (name "RX2") (class "Default")
      (node (ref "E_1") (pin "22") (pinfunction "GP134_UART_2_RX_22") (pintype "bidirectional"))
      (node (ref "U1") (pin "7") (pinfunction "A6_7") (pintype "bidirectional"))
      (node (ref "U8") (pin "22") (pinfunction "GP134_UART_2_RX_22") (pintype "bidirectional"))
    )
    (net (code "95") (name "RX_5V") (class "Default")
      (node (ref "R20") (pin "2") (pinfunction "2_2") (pintype "passive"))
      (node (ref "U1") (pin "15") (pinfunction "B5_15") (pintype "bidirectional"))
      (node (ref "U5") (pin "12") (pinfunction "RB5/AN11/RX/DT_12") (pintype "bidirectional"))
    )
    (net (code "96") (name "SCK") (class "Default")
      (node (ref "U7") (pin "5") (pinfunction "SCK_5") (pintype "bidirectional"))
      (node (ref "U9") (pin "P$12") (pinfunction "B7_P$12") (pintype "bidirectional"))
      (node (ref "U9") (pin "P$17") (pinfunction "B4_P$17") (pintype "bidirectional"))
    )
    (net (code "97") (name "SCLA1") (class "Default")
      (node (ref "E_1") (pin "41") (pinfunction "GP19_I2C_1_SCL_41") (pintype "bidirectional"))
      (node (ref "R4") (pin "1") (pinfunction "1_1") (pintype "passive"))
      (node (ref "U15") (pin "2") (pinfunction "SCLA_2") (pintype "bidirectional"))
      (node (ref "U16") (pin "2") (pinfunction "SCLA_2") (pintype "bidirectional"))
      (node (ref "U8") (pin "41") (pinfunction "GP19_I2C_1_SCL_41") (pintype "bidirectional"))
    )
    (net (code "98") (name "SCLA2") (class "Default")
      (node (ref "E_1") (pin "45") (pinfunction "GP27_I2C_6_SCL_45") (pintype "bidirectional"))
      (node (ref "R7") (pin "1") (pinfunction "1_1") (pintype "passive"))
      (node (ref "U12") (pin "2") (pinfunction "SCLA_2") (pintype "bidirectional"))
      (node (ref "U6") (pin "2") (pinfunction "SCLA_2") (pintype "bidirectional"))
      (node (ref "U8") (pin "45") (pinfunction "GP27_I2C_6_SCL_45") (pintype "bidirectional"))
    )
    (net (code "99") (name "SCLB1") (class "Default")
      (node (ref "I2C1_ACC") (pin "4") (pinfunction "S_4") (pintype "passive"))
      (node (ref "I2C1_H") (pin "4") (pinfunction "S_4") (pintype "passive"))
      (node (ref "I2C1_IR1") (pin "4") (pinfunction "S_4") (pintype "passive"))
      (node (ref "I2C1_IR2") (pin "4") (pinfunction "S_4") (pintype "passive"))
      (node (ref "I2C1_L1") (pin "4") (pinfunction "S_4") (pintype "passive"))
      (node (ref "I2C1_L2") (pin "4") (pinfunction "S_4") (pintype "passive"))
      (node (ref "I2C1_P") (pin "4") (pinfunction "S_4") (pintype "passive"))
      (node (ref "R5") (pin "1") (pinfunction "1_1") (pintype "passive"))
      (node (ref "U15") (pin "7") (pinfunction "SCLB_7") (pintype "bidirectional"))
    )
    (net (code "100") (name "SCLB2") (class "Default")
      (node (ref "I2C6_AIR") (pin "4") (pinfunction "S_4") (pintype "passive"))
      (node (ref "I2C6_IR1") (pin "4") (pinfunction "S_4") (pintype "passive"))
      (node (ref "I2C6_IR2") (pin "4") (pinfunction "S_4") (pintype "passive"))
      (node (ref "I2C6_L1") (pin "4") (pinfunction "S_4") (pintype "passive"))
      (node (ref "I2C6_L2") (pin "4") (pinfunction "S_4") (pintype "passive"))
      (node (ref "R8") (pin "1") (pinfunction "1_1") (pintype "passive"))
      (node (ref "U12") (pin "7") (pinfunction "SCLB_7") (pintype "bidirectional"))
    )
    (net (code "101") (name "SCLB2_3D") (class "Default")
      (node (ref "3DPAD_1") (pin "6") (pinfunction "S_6") (pintype "passive"))
      (node (ref "R39") (pin "1") (pinfunction "1_1") (pintype "passive"))
      (node (ref "U6") (pin "7") (pinfunction "SCLB_7") (pintype "bidirectional"))
    )
    (net (code "102") (name "SCL_5V") (class "Default")
      (node (ref "R25") (pin "1") (pinfunction "1_1") (pintype "passive"))
      (node (ref "U16") (pin "7") (pinfunction "SCLB_7") (pintype "bidirectional"))
      (node (ref "U5") (pin "11") (pinfunction "RB6/SCK/SCL_11") (pintype "bidirectional"))
    )
    (net (code "103") (name "SDAA1") (class "Default")
      (node (ref "E_1") (pin "43") (pinfunction "GP20_I2C_1_SDA_43") (pintype "bidirectional"))
      (node (ref "R2") (pin "1") (pinfunction "1_1") (pintype "passive"))
      (node (ref "U15") (pin "3") (pinfunction "SDAA_3") (pintype "bidirectional"))
      (node (ref "U16") (pin "3") (pinfunction "SDAA_3") (pintype "bidirectional"))
      (node (ref "U8") (pin "43") (pinfunction "GP20_I2C_1_SDA_43") (pintype "bidirectional"))
    )
    (net (code "104") (name "SDAA2") (class "Default")
      (node (ref "E_1") (pin "47") (pinfunction "GP28_I2C_6_SDA_47") (pintype "bidirectional"))
      (node (ref "R6") (pin "1") (pinfunction "1_1") (pintype "passive"))
      (node (ref "U12") (pin "3") (pinfunction "SDAA_3") (pintype "bidirectional"))
      (node (ref "U6") (pin "3") (pinfunction "SDAA_3") (pintype "bidirectional"))
      (node (ref "U8") (pin "47") (pinfunction "GP28_I2C_6_SDA_47") (pintype "bidirectional"))
    )
    (net (code "105") (name "SDAB1") (class "Default")
      (node (ref "I2C1_ACC") (pin "5") (pinfunction "S_5") (pintype "passive"))
      (node (ref "I2C1_H") (pin "5") (pinfunction "S_5") (pintype "passive"))
      (node (ref "I2C1_IR1") (pin "5") (pinfunction "S_5") (pintype "passive"))
      (node (ref "I2C1_IR2") (pin "5") (pinfunction "S_5") (pintype "passive"))
      (node (ref "I2C1_L1") (pin "5") (pinfunction "S_5") (pintype "passive"))
      (node (ref "I2C1_L2") (pin "5") (pinfunction "S_5") (pintype "passive"))
      (node (ref "I2C1_P") (pin "5") (pinfunction "S_5") (pintype "passive"))
      (node (ref "R10") (pin "1") (pinfunction "1_1") (pintype "passive"))
      (node (ref "U15") (pin "6") (pinfunction "SDAB_6") (pintype "bidirectional"))
    )
    (net (code "106") (name "SDAB2") (class "Default")
      (node (ref "I2C6_AIR") (pin "5") (pinfunction "S_5") (pintype "passive"))
      (node (ref "I2C6_IR1") (pin "5") (pinfunction "S_5") (pintype "passive"))
      (node (ref "I2C6_IR2") (pin "5") (pinfunction "S_5") (pintype "passive"))
      (node (ref "I2C6_L1") (pin "5") (pinfunction "S_5") (pintype "passive"))
      (node (ref "I2C6_L2") (pin "5") (pinfunction "S_5") (pintype "passive"))
      (node (ref "R9") (pin "1") (pinfunction "1_1") (pintype "passive"))
      (node (ref "U12") (pin "6") (pinfunction "SDAB_6") (pintype "bidirectional"))
    )
    (net (code "107") (name "SDAB2_3D") (class "Default")
      (node (ref "3DPAD_1") (pin "5") (pinfunction "S_5") (pintype "passive"))
      (node (ref "R40") (pin "1") (pinfunction "1_1") (pintype "passive"))
      (node (ref "U6") (pin "6") (pinfunction "SDAB_6") (pintype "bidirectional"))
    )
    (net (code "108") (name "SDA_5V") (class "Default")
      (node (ref "R26") (pin "1") (pinfunction "1_1") (pintype "passive"))
      (node (ref "U16") (pin "6") (pinfunction "SDAB_6") (pintype "bidirectional"))
      (node (ref "U5") (pin "13") (pinfunction "RB4/AN10/SDI/SDA_13") (pintype "bidirectional"))
    )
    (net (code "109") (name "TX1") (class "Default")
      (node (ref "E_1") (pin "46") (pinfunction "GP131_UART_1_TX_46") (pintype "bidirectional"))
      (node (ref "U1") (pin "8") (pinfunction "A7_8") (pintype "bidirectional"))
      (node (ref "U8") (pin "46") (pinfunction "GP131_UART_1_TX_46") (pintype "bidirectional"))
    )
    (net (code "110") (name "TX1_HI") (class "Default")
      (node (ref "TP11") (pin "TP") (pinfunction "TP_TP") (pintype "input"))
      (node (ref "U1") (pin "13") (pinfunction "B7_13") (pintype "bidirectional"))
    )
    (net (code "111") (name "TX2") (class "Default")
      (node (ref "E_1") (pin "27") (pinfunction "GP135_UART_2_TX_27") (pintype "bidirectional"))
      (node (ref "U1") (pin "6") (pinfunction "A5_6") (pintype "bidirectional"))
      (node (ref "U8") (pin "27") (pinfunction "GP135_UART_2_TX_27") (pintype "bidirectional"))
    )
    (net (code "112") (name "TX_5V") (class "Default")
      (node (ref "R19") (pin "2") (pinfunction "2_2") (pintype "passive"))
      (node (ref "U1") (pin "14") (pinfunction "B6_14") (pintype "bidirectional"))
      (node (ref "U5") (pin "10") (pinfunction "RB7/TX/CK_10") (pintype "bidirectional"))
    )
    (net (code "113") (name "VBUS") (class "Default")
      (node (ref "C11") (pin "1") (pinfunction "1_1") (pintype "passive"))
      (node (ref "E_1") (pin "20") (pinfunction "USB_VBUS_20") (pintype "bidirectional"))
      (node (ref "U4") (pin "6") (pinfunction "VOUT_6") (pintype "bidirectional"))
      (node (ref "U8") (pin "20") (pinfunction "USB_VBUS_20") (pintype "bidirectional"))
    )
    (net (code "114") (name "VIN5V") (class "Default")
      (node (ref "C12") (pin "1") (pinfunction "1_1") (pintype "passive"))
      (node (ref "C16") (pin "2") (pinfunction "2_2") (pintype "passive"))
      (node (ref "C18") (pin "1") (pinfunction "1_1") (pintype "passive"))
      (node (ref "C2") (pin "1") (pinfunction "1_1") (pintype "passive"))
      (node (ref "C35") (pin "1") (pinfunction "1_1") (pintype "passive"))
      (node (ref "C41") (pin "2") (pinfunction "2_2") (pintype "passive"))
      (node (ref "C42") (pin "1") (pinfunction "1_1") (pintype "passive"))
      (node (ref "C43") (pin "1") (pinfunction "1_1") (pintype "passive"))
      (node (ref "D1") (pin "C") (pinfunction "C_C") (pintype "passive"))
      (node (ref "D3") (pin "A") (pinfunction "A_A") (pintype "passive"))
      (node (ref "I2C6_AIR") (pin "1") (pinfunction "S_1") (pintype "passive"))
      (node (ref "JP3") (pin "1") (pinfunction "1_1") (pintype "passive"))
      (node (ref "R19") (pin "1") (pinfunction "1_1") (pintype "passive"))
      (node (ref "R20") (pin "1") (pinfunction "1_1") (pintype "passive"))
      (node (ref "R25") (pin "2") (pinfunction "2_2") (pintype "passive"))
      (node (ref "R26") (pin "2") (pinfunction "2_2") (pintype "passive"))
      (node (ref "R28") (pin "1") (pinfunction "1_1") (pintype "passive"))
      (node (ref "R37") (pin "2") (pinfunction "2_2") (pintype "passive"))
      (node (ref "R41") (pin "1") (pinfunction "1_1") (pintype "passive"))
      (node (ref "U1") (pin "19") (pinfunction "VCCB_19") (pintype "bidirectional"))
      (node (ref "U11") (pin "1") (pinfunction "VOUT_1") (pintype "bidirectional"))
      (node (ref "U11") (pin "12") (pinfunction "FB_12") (pintype "bidirectional"))
      (node (ref "U16") (pin "8") (pinfunction "VCCB_8") (pintype "bidirectional"))
      (node (ref "U4") (pin "1") (pinfunction "VIN_1") (pintype "bidirectional"))
      (node (ref "U5") (pin "17") (pinfunction "VUSB_17") (pintype "bidirectional"))
    )
    (net (code "115") (name "VSYS") (class "Default")
      (node (ref "C20") (pin "1") (pinfunction "1_1") (pintype "passive"))
      (node (ref "E_1") (pin "14") (pinfunction "DCIN_14") (pintype "bidirectional"))
      (node (ref "E_1") (pin "2") (pinfunction "VSYS_2") (pintype "bidirectional"))
      (node (ref "E_1") (pin "4") (pinfunction "VSYS_4") (pintype "bidirectional"))
      (node (ref "E_1") (pin "6") (pinfunction "VSYS_6") (pintype "bidirectional"))
      (node (ref "R16") (pin "1") (pinfunction "1_1") (pintype "passive"))
      (node (ref "R22") (pin "1") (pinfunction "1_1") (pintype "passive"))
      (node (ref "U3") (pin "10") (pinfunction "OUT_10") (pintype "bidirectional"))
      (node (ref "U3") (pin "11") (pinfunction "OUT_11") (pintype "bidirectional"))
      (node (ref "U3") (pin "5") (pinfunction "EN2_5") (pintype "bidirectional"))
      (node (ref "U8") (pin "14") (pinfunction "DCIN_14") (pintype "bidirectional"))
      (node (ref "U8") (pin "2") (pinfunction "VSYS_2") (pintype "bidirectional"))
      (node (ref "U8") (pin "4") (pinfunction "VSYS_4") (pintype "bidirectional"))
      (node (ref "U8") (pin "6") (pinfunction "VSYS_6") (pintype "bidirectional"))
    )
    (net (code "116") (name "V_1P80") (class "Default")
      (node (ref "C1") (pin "1") (pinfunction "1_1") (pintype "passive"))
      (node (ref "C13") (pin "1") (pinfunction "1_1") (pintype "passive"))
      (node (ref "C14") (pin "1") (pinfunction "1_1") (pintype "passive"))
      (node (ref "C21") (pin "1") (pinfunction "1_1") (pintype "passive"))
      (node (ref "C22") (pin "1") (pinfunction "1_1") (pintype "passive"))
      (node (ref "C23") (pin "1") (pinfunction "1_1") (pintype "passive"))
      (node (ref "C24") (pin "2") (pinfunction "2_2") (pintype "passive"))
      (node (ref "C3") (pin "1") (pinfunction "1_1") (pintype "passive"))
      (node (ref "C36") (pin "2") (pinfunction "2_2") (pintype "passive"))
      (node (ref "C38") (pin "2") (pinfunction "2_2") (pintype "passive"))
      (node (ref "C40") (pin "2") (pinfunction "2_2") (pintype "passive"))
      (node (ref "E_1") (pin "12") (pinfunction "1.8V_12") (pintype "bidirectional"))
      (node (ref "JP3") (pin "2") (pinfunction "2_2") (pintype "passive"))
      (node (ref "R2") (pin "2") (pinfunction "2_2") (pintype "passive"))
      (node (ref "R29") (pin "1") (pinfunction "1_1") (pintype "passive"))
      (node (ref "R31") (pin "1") (pinfunction "1_1") (pintype "passive"))
      (node (ref "R4") (pin "2") (pinfunction "2_2") (pintype "passive"))
      (node (ref "R6") (pin "2") (pinfunction "2_2") (pintype "passive"))
      (node (ref "R7") (pin "2") (pinfunction "2_2") (pintype "passive"))
      (node (ref "U1") (pin "10") (pinfunction "OE_10") (pintype "bidirectional"))
      (node (ref "U1") (pin "2") (pinfunction "VCCA_2") (pintype "bidirectional"))
      (node (ref "U12") (pin "1") (pinfunction "VCCA_1") (pintype "bidirectional"))
      (node (ref "U15") (pin "1") (pinfunction "VCCA_1") (pintype "bidirectional"))
      (node (ref "U16") (pin "1") (pinfunction "VCCA_1") (pintype "bidirectional"))
      (node (ref "U2") (pin "10") (pinfunction "OE_10") (pintype "bidirectional"))
      (node (ref "U2") (pin "2") (pinfunction "VCCA_2") (pintype "bidirectional"))
      (node (ref "U6") (pin "1") (pinfunction "VCCA_1") (pintype "bidirectional"))
      (node (ref "U8") (pin "12") (pinfunction "1.8V_12") (pintype "bidirectional"))
      (node (ref "U9") (pin "P$5") (pinfunction "VCCA_P$5") (pintype "bidirectional"))
      (node (ref "U9") (pin "P$6") (pinfunction "OE_P$6") (pintype "bidirectional"))
    )
    (net (code "117") (name "V_3.3V") (class "Default")
      (node (ref "3DPAD_1") (pin "3") (pinfunction "S_3") (pintype "passive"))
      (node (ref "C15") (pin "1") (pinfunction "1_1") (pintype "passive"))
      (node (ref "C17") (pin "1") (pinfunction "1_1") (pintype "passive"))
      (node (ref "C25") (pin "2") (pinfunction "2_2") (pintype "passive"))
      (node (ref "C26") (pin "1") (pinfunction "1_1") (pintype "passive"))
      (node (ref "C27") (pin "1") (pinfunction "1_1") (pintype "passive"))
      (node (ref "C29") (pin "1") (pinfunction "1_1") (pintype "passive"))
      (node (ref "C30") (pin "1") (pinfunction "1_1") (pintype "passive"))
      (node (ref "C31") (pin "1") (pinfunction "1_1") (pintype "passive"))
      (node (ref "C32") (pin "1") (pinfunction "1_1") (pintype "passive"))
      (node (ref "C33") (pin "1") (pinfunction "1_1") (pintype "passive"))
      (node (ref "C37") (pin "2") (pinfunction "2_2") (pintype "passive"))
      (node (ref "C39") (pin "2") (pinfunction "2_2") (pintype "passive"))
      (node (ref "C4") (pin "1") (pinfunction "1_1") (pintype "passive"))
      (node (ref "C5") (pin "1") (pinfunction "1_1") (pintype "passive"))
      (node (ref "C6") (pin "1") (pinfunction "1_1") (pintype "passive"))
      (node (ref "C7") (pin "1") (pinfunction "1_1") (pintype "passive"))
      (node (ref "C8") (pin "1") (pinfunction "1_1") (pintype "passive"))
      (node (ref "E_1") (pin "10") (pinfunction "3.3V_10") (pintype "bidirectional"))
      (node (ref "E_1") (pin "8") (pinfunction "3.3V_8") (pintype "bidirectional"))
      (node (ref "I2C1_ACC") (pin "1") (pinfunction "S_1") (pintype "passive"))
      (node (ref "I2C1_H") (pin "1") (pinfunction "S_1") (pintype "passive"))
      (node (ref "I2C1_IR1") (pin "1") (pinfunction "S_1") (pintype "passive"))
      (node (ref "I2C1_IR2") (pin "1") (pinfunction "S_1") (pintype "passive"))
      (node (ref "I2C1_L1") (pin "1") (pinfunction "S_1") (pintype "passive"))
      (node (ref "I2C1_L2") (pin "1") (pinfunction "S_1") (pintype "passive"))
      (node (ref "I2C1_P") (pin "1") (pinfunction "S_1") (pintype "passive"))
      (node (ref "I2C6_IR1") (pin "1") (pinfunction "S_1") (pintype "passive"))
      (node (ref "I2C6_IR2") (pin "1") (pinfunction "S_1") (pintype "passive"))
      (node (ref "I2C6_L1") (pin "1") (pinfunction "S_1") (pintype "passive"))
      (node (ref "I2C6_L2") (pin "1") (pinfunction "S_1") (pintype "passive"))
      (node (ref "JP3") (pin "3") (pinfunction "3_3") (pintype "passive"))
      (node (ref "R10") (pin "2") (pinfunction "2_2") (pintype "passive"))
      (node (ref "R39") (pin "2") (pinfunction "2_2") (pintype "passive"))
      (node (ref "R40") (pin "2") (pinfunction "2_2") (pintype "passive"))
      (node (ref "R5") (pin "2") (pinfunction "2_2") (pintype "passive"))
      (node (ref "R8") (pin "2") (pinfunction "2_2") (pintype "passive"))
      (node (ref "R9") (pin "2") (pinfunction "2_2") (pintype "passive"))
      (node (ref "U12") (pin "8") (pinfunction "VCCB_8") (pintype "bidirectional"))
      (node (ref "U15") (pin "8") (pinfunction "VCCB_8") (pintype "bidirectional"))
      (node (ref "U2") (pin "19") (pinfunction "VCCB_19") (pintype "bidirectional"))
      (node (ref "U6") (pin "8") (pinfunction "VCCB_8") (pintype "bidirectional"))
      (node (ref "U7") (pin "4") (pinfunction "VCC_4") (pintype "bidirectional"))
      (node (ref "U8") (pin "10") (pinfunction "3.3V_10") (pintype "bidirectional"))
      (node (ref "U8") (pin "8") (pinfunction "3.3V_8") (pintype "bidirectional"))
      (node (ref "U9") (pin "P$16") (pinfunction "VCCB_P$16") (pintype "bidirectional"))
    )
    (net (code "118") (name "V_PROG") (class "Default")
      (node (ref "C19") (pin "1") (pinfunction "1_1") (pintype "passive"))
      (node (ref "C28") (pin "1") (pinfunction "1_1") (pintype "passive"))
      (node (ref "D3") (pin "C") (pinfunction "C_C") (pintype "passive"))
      (node (ref "ICSP") (pin "1") (pinfunction "S_1") (pintype "passive"))
      (node (ref "U5") (pin "1") (pinfunction "VDD_1") (pintype "power_in"))
    )
    (net (code "119") (name "V_VAT") (class "Default")
      (node (ref "E_1") (pin "23") (pinfunction "V_VAT_BKUP_23") (pintype "bidirectional"))
      (node (ref "U8") (pin "23") (pinfunction "V_VAT_BKUP_23") (pintype "bidirectional"))
    )
    (net (code "120") (name "unconnected-(I2C1_ACCC-S-Pad3)") (class "Default")
      (node (ref "I2C1_ACC") (pin "3") (pinfunction "S_3") (pintype "passive"))
    )
    (net (code "121") (name "unconnected-(I2C1_HC-S-Pad3)") (class "Default")
      (node (ref "I2C1_H") (pin "3") (pinfunction "S_3") (pintype "passive"))
    )
    (net (code "122") (name "unconnected-(I2C1_IR1C-S-Pad3)") (class "Default")
      (node (ref "I2C1_IR1") (pin "3") (pinfunction "S_3") (pintype "passive"))
    )
    (net (code "123") (name "unconnected-(I2C1_IR2C-S-Pad3)") (class "Default")
      (node (ref "I2C1_IR2") (pin "3") (pinfunction "S_3") (pintype "passive"))
    )
    (net (code "124") (name "unconnected-(I2C1_L1C-S-Pad3)") (class "Default")
      (node (ref "I2C1_L1") (pin "3") (pinfunction "S_3") (pintype "passive"))
    )
    (net (code "125") (name "unconnected-(I2C1_L2C-S-Pad3)") (class "Default")
      (node (ref "I2C1_L2") (pin "3") (pinfunction "S_3") (pintype "passive"))
    )
    (net (code "126") (name "unconnected-(I2C1_PC-S-Pad3)") (class "Default")
      (node (ref "I2C1_P") (pin "3") (pinfunction "S_3") (pintype "passive"))
    )
    (net (code "127") (name "unconnected-(I2C6_IR1C-S-Pad3)") (class "Default")
      (node (ref "I2C6_IR1") (pin "3") (pinfunction "S_3") (pintype "passive"))
    )
    (net (code "128") (name "unconnected-(I2C6_IR2C-S-Pad3)") (class "Default")
      (node (ref "I2C6_IR2") (pin "3") (pinfunction "S_3") (pintype "passive"))
    )
    (net (code "129") (name "unconnected-(I2C6_L1C-S-Pad3)") (class "Default")
      (node (ref "I2C6_L1") (pin "3") (pinfunction "S_3") (pintype "passive"))
    )
    (net (code "130") (name "unconnected-(I2C6_L2C-S-Pad3)") (class "Default")
      (node (ref "I2C6_L2") (pin "3") (pinfunction "S_3") (pintype "passive"))
    )
    (net (code "131") (name "unconnected-(U3-~{PGOOD}-Pad7)") (class "Default")
      (node (ref "U3") (pin "7") (pinfunction "~{PGOOD}_7") (pintype "bidirectional"))
    )
    (net (code "132") (name "unconnected-(U5-RC2{slash}AN6{slash}P1D{slash}C12IN2-{slash}CVREF{slash}INT2-Pad14)") (class "Default")
      (node (ref "U5") (pin "14") (pinfunction "RC2/AN6/P1D/C12IN2-/CVREF/INT2_14") (pintype "bidirectional"))
    )
    (net (code "133") (name "unconnected-(U5-RC7{slash}AN9{slash}SDO{slash}T1OSCO-Pad9)") (class "Default")
      (node (ref "U5") (pin "9") (pinfunction "RC7/AN9/SDO/T1OSCO_9") (pintype "bidirectional"))
    )
    (net (code "134") (name "unconnected-(U6-EN-Pad5)") (class "Default")
      (node (ref "U6") (pin "5") (pinfunction "EN_5") (pintype "bidirectional"))
    )
    (net (code "135") (name "unconnected-(U7-SHIELD-PadCD2)") (class "Default")
      (node (ref "U7") (pin "CD2") (pinfunction "SHIELD_CD2") (pintype "bidirectional"))
    )
    (net (code "136") (name "unconnected-(U9-A8-PadP$10)") (class "Default")
      (node (ref "U9") (pin "P$10") (pinfunction "A8_P$10") (pintype "bidirectional"))
    )
    (net (code "137") (name "unconnected-(U9-B8-PadP$11)") (class "Default")
      (node (ref "U9") (pin "P$11") (pinfunction "B8_P$11") (pintype "bidirectional"))
    )
    (net (code "138") (name "unconnected-(U12-EN-Pad5)") (class "Default")
      (node (ref "U12") (pin "5") (pinfunction "EN_5") (pintype "bidirectional"))
    )
    (net (code "139") (name "unconnected-(U15-EN-Pad5)") (class "Default")
      (node (ref "U15") (pin "5") (pinfunction "EN_5") (pintype "bidirectional"))
    )
    (net (code "140") (name "unconnected-(U16-EN-Pad5)") (class "Default")
      (node (ref "U16") (pin "5") (pinfunction "EN_5") (pintype "bidirectional"))
    )
  )
)
